# cpu-68000.net
KiCad netlist of a schematic drawn in EAGLE
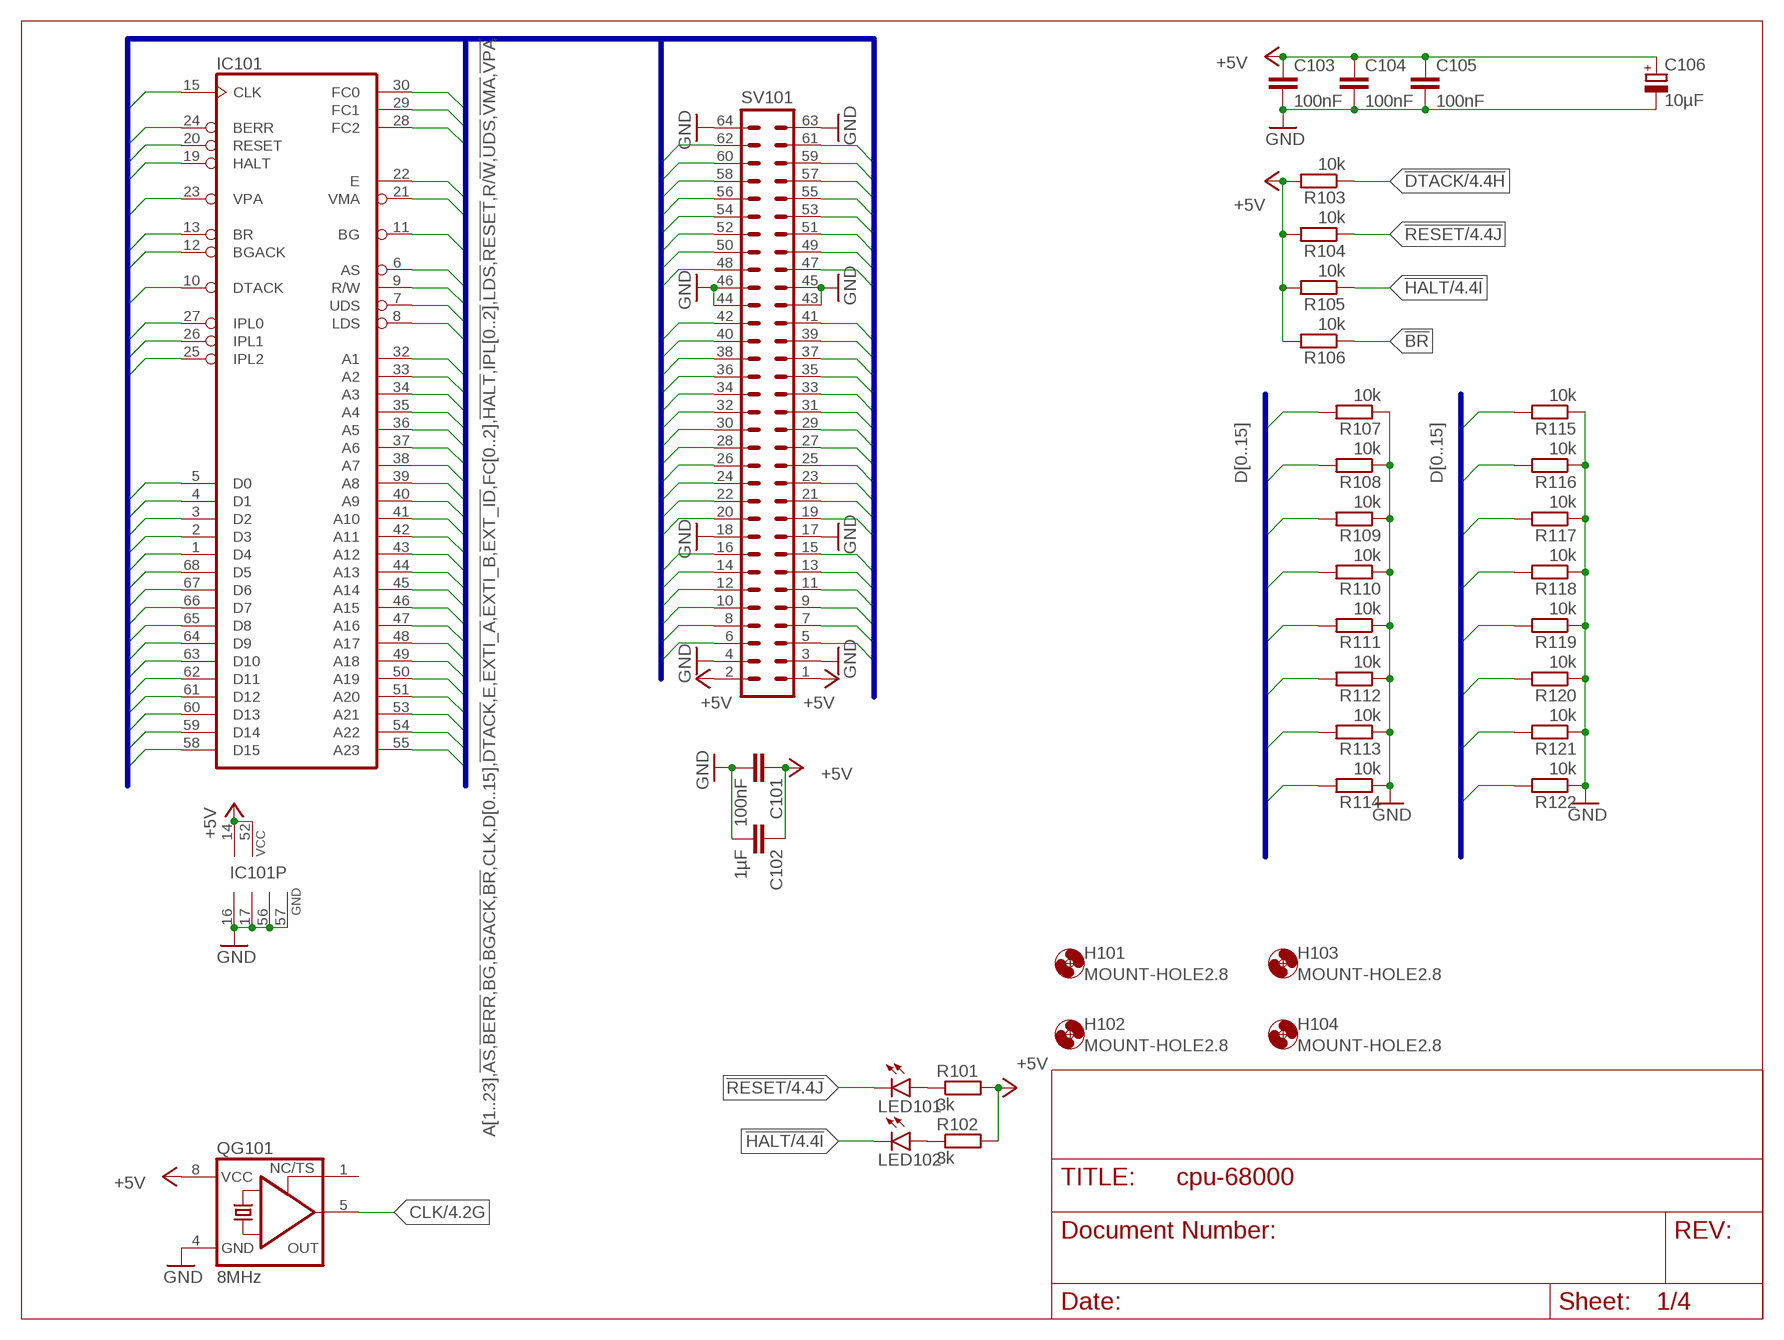
[diagram p0: schematic, sheet 1]
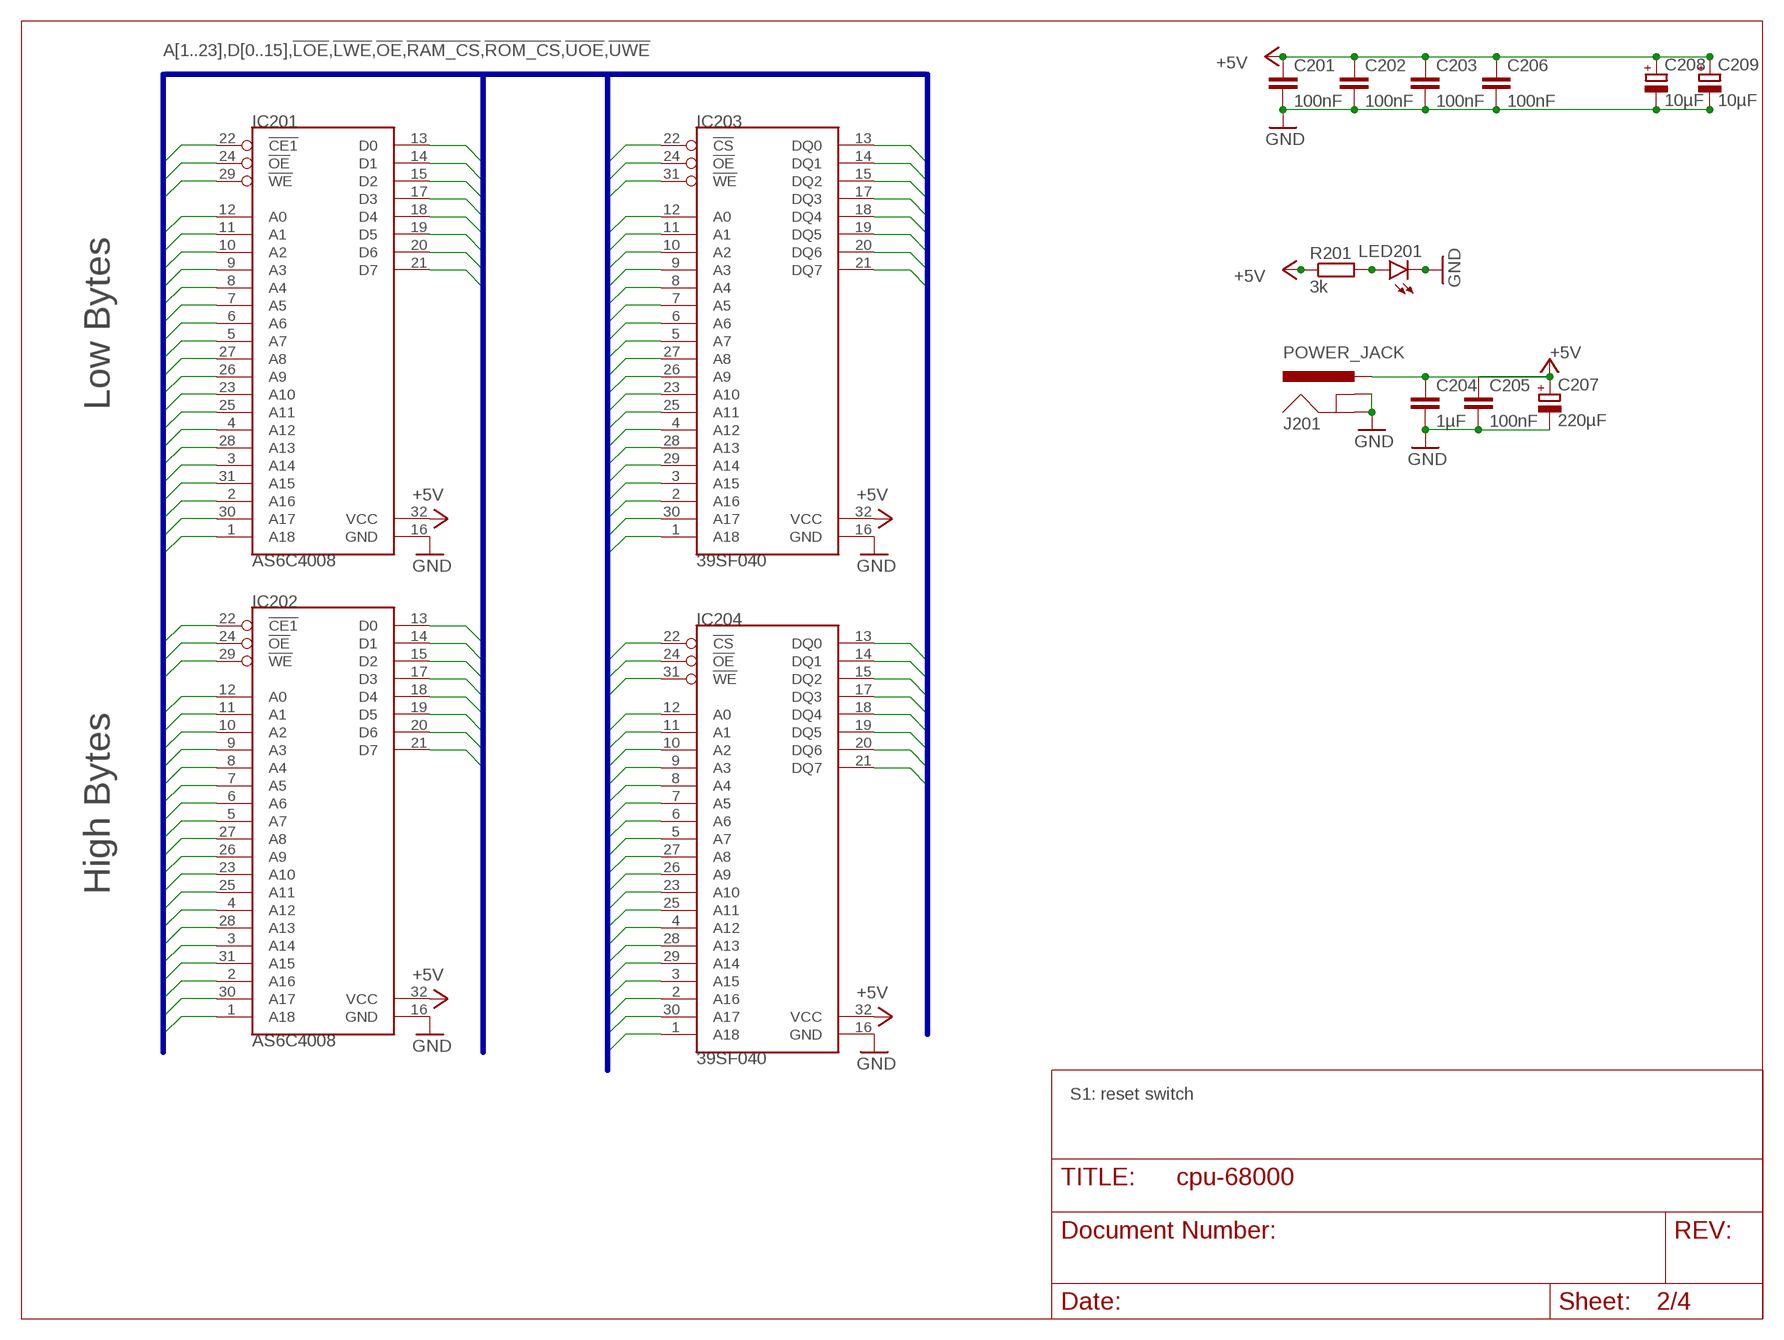
[diagram p1: schematic, sheet 2]
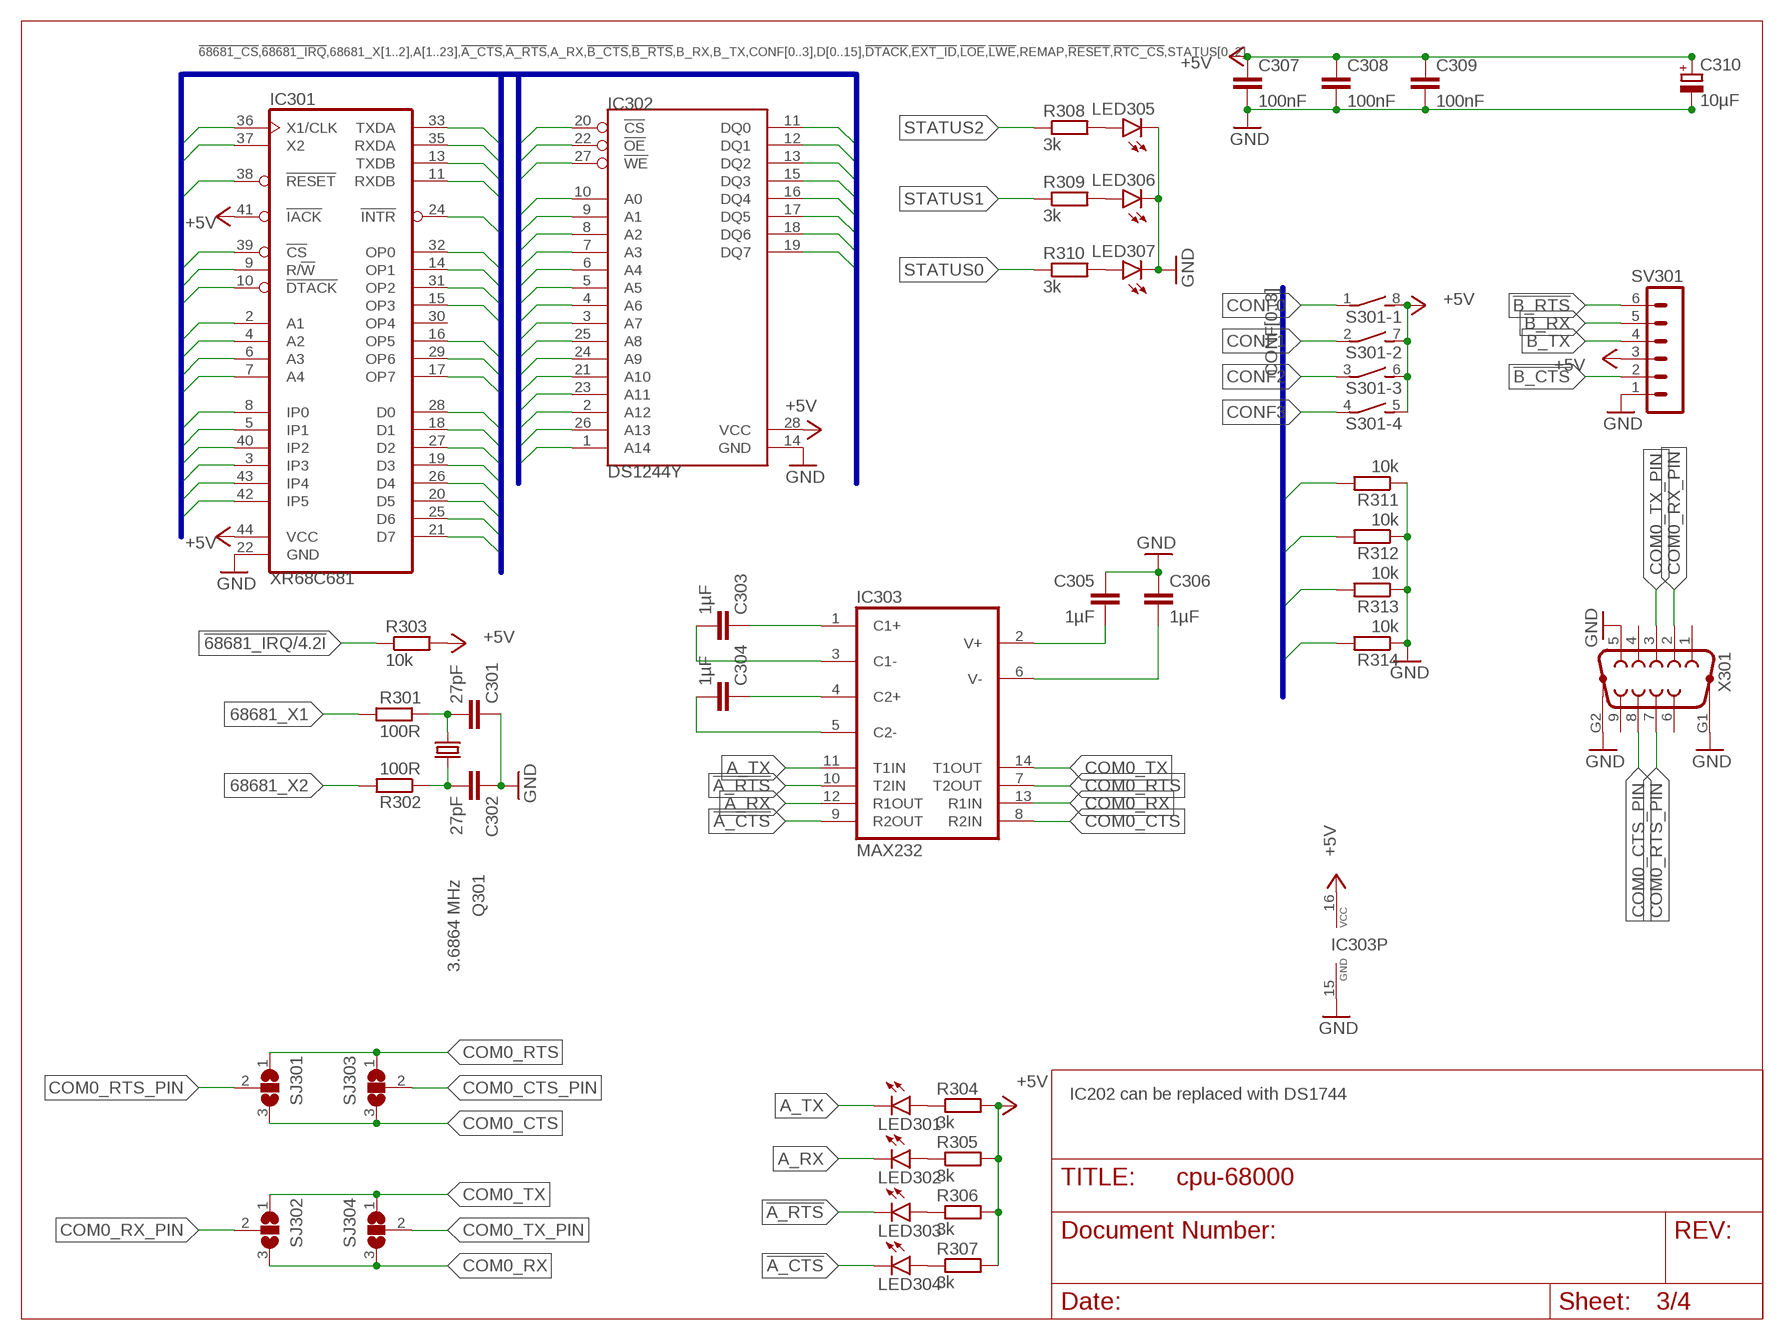
[diagram p2: schematic, sheet 3]
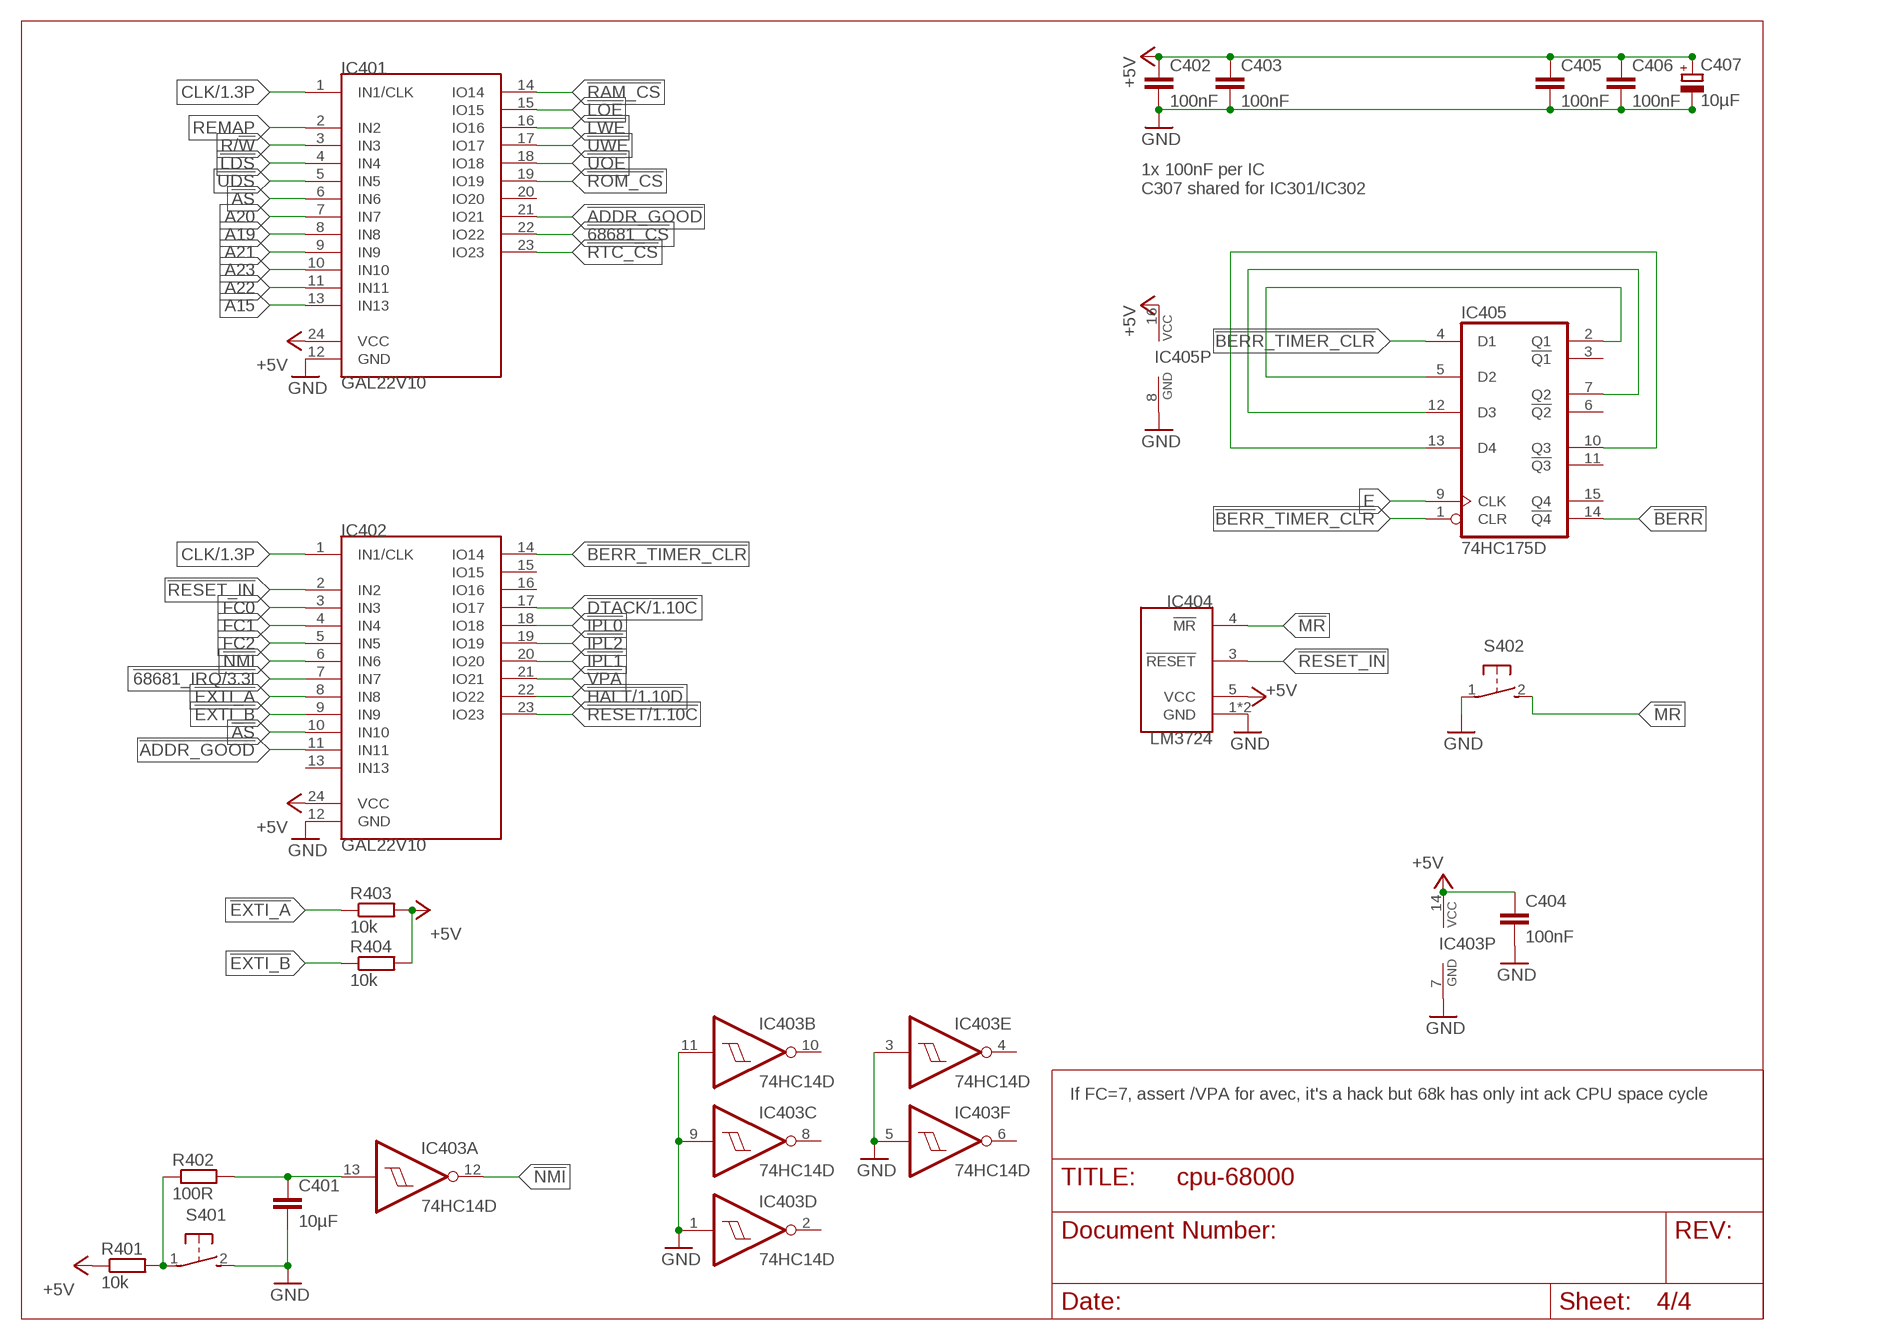
[diagram p3: schematic, sheet 4]

(export (version "E")
  (design (tool "Eeschema 10.0.6"))
  (components
    (comp (ref "C301")
      (value "27pF")
      (footprint "eagle-import:C0805")
      (libsource (lib "eagle-import") (part "C-EUC0805"))
    )
    (comp (ref "C302")
      (value "27pF")
      (footprint "eagle-import:C0805")
      (libsource (lib "eagle-import") (part "C-EUC0805"))
    )
    (comp (ref "C303")
      (value "1µF")
      (footprint "eagle-import:C0805")
      (libsource (lib "eagle-import") (part "C-EUC0805"))
    )
    (comp (ref "C304")
      (value "1µF")
      (footprint "eagle-import:C0805")
      (libsource (lib "eagle-import") (part "C-EUC0805"))
    )
    (comp (ref "C305")
      (value "1µF")
      (footprint "eagle-import:C0805")
      (libsource (lib "eagle-import") (part "C-EUC0805"))
    )
    (comp (ref "C306")
      (value "1µF")
      (footprint "eagle-import:C0805")
      (libsource (lib "eagle-import") (part "C-EUC0805"))
    )
    (comp (ref "C307")
      (value "100nF")
      (footprint "eagle-import:C0805")
      (libsource (lib "eagle-import") (part "C-EUC0805"))
    )
    (comp (ref "C308")
      (value "100nF")
      (footprint "eagle-import:C0805")
      (libsource (lib "eagle-import") (part "C-EUC0805"))
    )
    (comp (ref "C309")
      (value "100nF")
      (footprint "eagle-import:C0805")
      (libsource (lib "eagle-import") (part "C-EUC0805"))
    )
    (comp (ref "C310")
      (value "10µF")
      (footprint "eagle-import:SMC_B")
      (libsource (lib "eagle-import") (part "CPOL-EUSMCB"))
    )
    (comp (ref "IC301")
      (value "XR68C681")
      (footprint "eagle-import:PLCC-S44")
      (libsource (lib "eagle-import") (part "MC68681PLCC44-SOCKET"))
    )
    (comp (ref "IC302")
      (value "DS1244Y")
      (footprint "eagle-import:DIL28-6")
      (libsource (lib "eagle-import") (part "DS1244EDIP-28"))
    )
    (comp (ref "IC303")
      (value "MAX232")
      (footprint "eagle-import:DIL16")
      (fields
        (field (name "MF") "MAXIM")
        (field (name "MPN") "MAX232ACPE+")
        (field (name "MOUSER") "595-MAX232ECN")
        (field (name "MOUSER_SOCKET") "575-1104731641001000")
      )
      (libsource (lib "eagle-import") (part "MAX232"))
    )
    (comp (ref "LED301")
      (value "LEDCHIPLED_1206")
      (footprint "eagle-import:CHIPLED_1206")
      (libsource (lib "eagle-import") (part "LEDCHIPLED_1206"))
    )
    (comp (ref "LED302")
      (value "LEDCHIPLED_1206")
      (footprint "eagle-import:CHIPLED_1206")
      (libsource (lib "eagle-import") (part "LEDCHIPLED_1206"))
    )
    (comp (ref "LED303")
      (value "LEDCHIPLED_1206")
      (footprint "eagle-import:CHIPLED_1206")
      (libsource (lib "eagle-import") (part "LEDCHIPLED_1206"))
    )
    (comp (ref "LED304")
      (value "LEDCHIPLED_1206")
      (footprint "eagle-import:CHIPLED_1206")
      (libsource (lib "eagle-import") (part "LEDCHIPLED_1206"))
    )
    (comp (ref "LED305")
      (value "LEDCHIPLED_1206")
      (footprint "eagle-import:CHIPLED_1206")
      (libsource (lib "eagle-import") (part "LEDCHIPLED_1206"))
    )
    (comp (ref "LED306")
      (value "LEDCHIPLED_1206")
      (footprint "eagle-import:CHIPLED_1206")
      (libsource (lib "eagle-import") (part "LEDCHIPLED_1206"))
    )
    (comp (ref "LED307")
      (value "LEDCHIPLED_1206")
      (footprint "eagle-import:CHIPLED_1206")
      (libsource (lib "eagle-import") (part "LEDCHIPLED_1206"))
    )
    (comp (ref "Q301")
      (value "3.6864 MHz")
      (footprint "eagle-import:HC49_S")
      (libsource (lib "eagle-import") (part "CRYSTALHC49S"))
    )
    (comp (ref "R301")
      (value "100R")
      (footprint "eagle-import:R2012")
      (libsource (lib "eagle-import") (part "R-EU_R2012"))
    )
    (comp (ref "R302")
      (value "100R")
      (footprint "eagle-import:R2012")
      (libsource (lib "eagle-import") (part "R-EU_R2012"))
    )
    (comp (ref "R303")
      (value "10k")
      (footprint "eagle-import:R2012")
      (libsource (lib "eagle-import") (part "R-EU_R2012"))
    )
    (comp (ref "R304")
      (value "3k")
      (footprint "eagle-import:R2012")
      (libsource (lib "eagle-import") (part "R-EU_R2012"))
    )
    (comp (ref "R305")
      (value "3k")
      (footprint "eagle-import:R2012")
      (libsource (lib "eagle-import") (part "R-EU_R2012"))
    )
    (comp (ref "R306")
      (value "3k")
      (footprint "eagle-import:R2012")
      (libsource (lib "eagle-import") (part "R-EU_R2012"))
    )
    (comp (ref "R307")
      (value "3k")
      (footprint "eagle-import:R2012")
      (libsource (lib "eagle-import") (part "R-EU_R2012"))
    )
    (comp (ref "R308")
      (value "3k")
      (footprint "eagle-import:R2012")
      (libsource (lib "eagle-import") (part "R-EU_R2012"))
    )
    (comp (ref "R309")
      (value "3k")
      (footprint "eagle-import:R2012")
      (libsource (lib "eagle-import") (part "R-EU_R2012"))
    )
    (comp (ref "R310")
      (value "3k")
      (footprint "eagle-import:R2012")
      (libsource (lib "eagle-import") (part "R-EU_R2012"))
    )
    (comp (ref "R311")
      (value "10k")
      (footprint "eagle-import:R2012")
      (libsource (lib "eagle-import") (part "R-EU_R2012"))
    )
    (comp (ref "R312")
      (value "10k")
      (footprint "eagle-import:R2012")
      (libsource (lib "eagle-import") (part "R-EU_R2012"))
    )
    (comp (ref "R313")
      (value "10k")
      (footprint "eagle-import:R2012")
      (libsource (lib "eagle-import") (part "R-EU_R2012"))
    )
    (comp (ref "R314")
      (value "10k")
      (footprint "eagle-import:R2012")
      (libsource (lib "eagle-import") (part "R-EU_R2012"))
    )
    (comp (ref "S301")
      (value "DIP04S")
      (footprint "eagle-import:DIP04S")
      (fields (field (name "MOUSER") "653-A6FR-4104"))
      (libsource (lib "eagle-import") (part "DIP04S"))
    )
    (comp (ref "SJ301")
      (value "SJ2WW")
      (footprint "eagle-import:SJ_2W")
      (libsource (lib "eagle-import") (part "SJ2WW"))
    )
    (comp (ref "SJ302")
      (value "SJ2WW")
      (footprint "eagle-import:SJ_2W")
      (libsource (lib "eagle-import") (part "SJ2WW"))
    )
    (comp (ref "SJ303")
      (value "SJ2WW")
      (footprint "eagle-import:SJ_2W")
      (libsource (lib "eagle-import") (part "SJ2WW"))
    )
    (comp (ref "SJ304")
      (value "SJ2WW")
      (footprint "eagle-import:SJ_2W")
      (libsource (lib "eagle-import") (part "SJ2WW"))
    )
    (comp (ref "SV301")
      (value "MA06-1")
      (footprint "eagle-import:MA06-1")
      (libsource (lib "eagle-import") (part "MA06-1"))
    )
    (comp (ref "X301")
      (value "F09HP")
      (footprint "eagle-import:F09HP")
      (libsource (lib "eagle-import") (part "F09HP"))
    )
    (comp (ref "C101")
      (value "100nF")
      (footprint "eagle-import:C0805")
      (libsource (lib "eagle-import") (part "C-EUC0805"))
    )
    (comp (ref "C102")
      (value "1µF")
      (footprint "eagle-import:C0805")
      (libsource (lib "eagle-import") (part "C-EUC0805"))
    )
    (comp (ref "C103")
      (value "100nF")
      (footprint "eagle-import:C0805")
      (libsource (lib "eagle-import") (part "C-EUC0805"))
    )
    (comp (ref "C104")
      (value "100nF")
      (footprint "eagle-import:C0805")
      (libsource (lib "eagle-import") (part "C-EUC0805"))
    )
    (comp (ref "C105")
      (value "100nF")
      (footprint "eagle-import:C0805")
      (libsource (lib "eagle-import") (part "C-EUC0805"))
    )
    (comp (ref "C106")
      (value "10µF")
      (footprint "eagle-import:SMC_B")
      (libsource (lib "eagle-import") (part "CPOL-EUSMCB"))
    )
    (comp (ref "H101")
      (value "MOUNT-HOLE2.8")
      (footprint "eagle-import:2,8")
      (libsource (lib "eagle-import") (part "MOUNT-HOLE2.8"))
    )
    (comp (ref "H102")
      (value "MOUNT-HOLE2.8")
      (footprint "eagle-import:2,8")
      (libsource (lib "eagle-import") (part "MOUNT-HOLE2.8"))
    )
    (comp (ref "H103")
      (value "MOUNT-HOLE2.8")
      (footprint "eagle-import:2,8")
      (libsource (lib "eagle-import") (part "MOUNT-HOLE2.8"))
    )
    (comp (ref "H104")
      (value "MOUNT-HOLE2.8")
      (footprint "eagle-import:2,8")
      (libsource (lib "eagle-import") (part "MOUNT-HOLE2.8"))
    )
    (comp (ref "IC101")
      (value "MC68000FN-SOC")
      (footprint "eagle-import:PLCC68SOCK")
      (fields (field (name "MOUSER_SOCKET") "940-44-068-24-000000"))
      (libsource (lib "eagle-import") (part "MC68000FN-SOC"))
    )
    (comp (ref "LED101")
      (value "LEDCHIPLED_1206")
      (footprint "eagle-import:CHIPLED_1206")
      (libsource (lib "eagle-import") (part "LEDCHIPLED_1206"))
    )
    (comp (ref "LED102")
      (value "LEDCHIPLED_1206")
      (footprint "eagle-import:CHIPLED_1206")
      (libsource (lib "eagle-import") (part "LEDCHIPLED_1206"))
    )
    (comp (ref "QG101")
      (value "8MHz")
      (footprint "eagle-import:DIL08S")
      (libsource (lib "eagle-import") (part "XO-8"))
    )
    (comp (ref "R101")
      (value "3k")
      (footprint "eagle-import:R2012")
      (libsource (lib "eagle-import") (part "R-EU_R2012"))
    )
    (comp (ref "R102")
      (value "3k")
      (footprint "eagle-import:R2012")
      (libsource (lib "eagle-import") (part "R-EU_R2012"))
    )
    (comp (ref "R103")
      (value "10k")
      (footprint "eagle-import:R2012")
      (libsource (lib "eagle-import") (part "R-EU_R2012"))
    )
    (comp (ref "R104")
      (value "10k")
      (footprint "eagle-import:R2012")
      (libsource (lib "eagle-import") (part "R-EU_R2012"))
    )
    (comp (ref "R105")
      (value "10k")
      (footprint "eagle-import:R2012")
      (libsource (lib "eagle-import") (part "R-EU_R2012"))
    )
    (comp (ref "R106")
      (value "10k")
      (footprint "eagle-import:R2012")
      (libsource (lib "eagle-import") (part "R-EU_R2012"))
    )
    (comp (ref "R107")
      (value "10k")
      (footprint "eagle-import:R2012")
      (libsource (lib "eagle-import") (part "R-EU_R2012"))
    )
    (comp (ref "R108")
      (value "10k")
      (footprint "eagle-import:R2012")
      (libsource (lib "eagle-import") (part "R-EU_R2012"))
    )
    (comp (ref "R109")
      (value "10k")
      (footprint "eagle-import:R2012")
      (libsource (lib "eagle-import") (part "R-EU_R2012"))
    )
    (comp (ref "R110")
      (value "10k")
      (footprint "eagle-import:R2012")
      (libsource (lib "eagle-import") (part "R-EU_R2012"))
    )
    (comp (ref "R111")
      (value "10k")
      (footprint "eagle-import:R2012")
      (libsource (lib "eagle-import") (part "R-EU_R2012"))
    )
    (comp (ref "R112")
      (value "10k")
      (footprint "eagle-import:R2012")
      (libsource (lib "eagle-import") (part "R-EU_R2012"))
    )
    (comp (ref "R113")
      (value "10k")
      (footprint "eagle-import:R2012")
      (libsource (lib "eagle-import") (part "R-EU_R2012"))
    )
    (comp (ref "R114")
      (value "10k")
      (footprint "eagle-import:R2012")
      (libsource (lib "eagle-import") (part "R-EU_R2012"))
    )
    (comp (ref "R115")
      (value "10k")
      (footprint "eagle-import:R2012")
      (libsource (lib "eagle-import") (part "R-EU_R2012"))
    )
    (comp (ref "R116")
      (value "10k")
      (footprint "eagle-import:R2012")
      (libsource (lib "eagle-import") (part "R-EU_R2012"))
    )
    (comp (ref "R117")
      (value "10k")
      (footprint "eagle-import:R2012")
      (libsource (lib "eagle-import") (part "R-EU_R2012"))
    )
    (comp (ref "R118")
      (value "10k")
      (footprint "eagle-import:R2012")
      (libsource (lib "eagle-import") (part "R-EU_R2012"))
    )
    (comp (ref "R119")
      (value "10k")
      (footprint "eagle-import:R2012")
      (libsource (lib "eagle-import") (part "R-EU_R2012"))
    )
    (comp (ref "R120")
      (value "10k")
      (footprint "eagle-import:R2012")
      (libsource (lib "eagle-import") (part "R-EU_R2012"))
    )
    (comp (ref "R121")
      (value "10k")
      (footprint "eagle-import:R2012")
      (libsource (lib "eagle-import") (part "R-EU_R2012"))
    )
    (comp (ref "R122")
      (value "10k")
      (footprint "eagle-import:R2012")
      (libsource (lib "eagle-import") (part "R-EU_R2012"))
    )
    (comp (ref "SV101")
      (value "ML64L")
      (footprint "eagle-import:ML64L")
      (libsource (lib "eagle-import") (part "ML64L"))
    )
    (comp (ref "C401")
      (value "10µF")
      (footprint "eagle-import:C0805")
      (libsource (lib "eagle-import") (part "C-EUC0805"))
    )
    (comp (ref "C402")
      (value "100nF")
      (footprint "eagle-import:C0805")
      (libsource (lib "eagle-import") (part "C-EUC0805"))
    )
    (comp (ref "C403")
      (value "100nF")
      (footprint "eagle-import:C0805")
      (libsource (lib "eagle-import") (part "C-EUC0805"))
    )
    (comp (ref "C404")
      (value "100nF")
      (footprint "eagle-import:C0805")
      (libsource (lib "eagle-import") (part "C-EUC0805"))
    )
    (comp (ref "C405")
      (value "100nF")
      (footprint "eagle-import:C0805")
      (libsource (lib "eagle-import") (part "C-EUC0805"))
    )
    (comp (ref "C406")
      (value "100nF")
      (footprint "eagle-import:C0805")
      (libsource (lib "eagle-import") (part "C-EUC0805"))
    )
    (comp (ref "C407")
      (value "10µF")
      (footprint "eagle-import:SMC_B")
      (libsource (lib "eagle-import") (part "CPOL-EUSMCB"))
    )
    (comp (ref "IC401")
      (value "GAL22V10")
      (footprint "eagle-import:DIL24S")
      (libsource (lib "eagle-import") (part "GAL22V10DIP24"))
    )
    (comp (ref "IC402")
      (value "GAL22V10")
      (footprint "eagle-import:DIL24S")
      (libsource (lib "eagle-import") (part "GAL22V10DIP24"))
    )
    (comp (ref "IC403")
      (value "74HC14D")
      (footprint "eagle-import:SO14")
      (fields (field (name "MOUSER") "771-74HC14D-T"))
      (libsource (lib "eagle-import") (part "7414DHC"))
    )
    (comp (ref "IC404")
      (value "LM3724")
      (footprint "eagle-import:SOT23-5")
      (libsource (lib "eagle-import") (part "LM3724"))
    )
    (comp (ref "IC405")
      (value "74HC175D")
      (footprint "eagle-import:SO16")
      (fields (field (name "MOUSER") "595-CD74HCT175M"))
      (libsource (lib "eagle-import") (part "74175DHC"))
    )
    (comp (ref "R401")
      (value "10k")
      (footprint "eagle-import:R2012")
      (libsource (lib "eagle-import") (part "R-EU_R2012"))
    )
    (comp (ref "R402")
      (value "100R")
      (footprint "eagle-import:R2012")
      (libsource (lib "eagle-import") (part "R-EU_R2012"))
    )
    (comp (ref "R403")
      (value "10k")
      (footprint "eagle-import:R2012")
      (libsource (lib "eagle-import") (part "R-EU_R2012"))
    )
    (comp (ref "R404")
      (value "10k")
      (footprint "eagle-import:R2012")
      (libsource (lib "eagle-import") (part "R-EU_R2012"))
    )
    (comp (ref "S401")
      (value "31-XX")
      (footprint "eagle-import:B3F-31XX")
      (fields (field (name "MPN") "B3F-3100") (field (name "SPICEPREFIX") "S"))
      (libsource (lib "eagle-import") (part "31-XX"))
    )
    (comp (ref "S402")
      (value "31-XX")
      (footprint "eagle-import:B3F-31XX")
      (fields (field (name "MPN") "B3F-3100"))
      (libsource (lib "eagle-import") (part "31-XX"))
    )
    (comp (ref "C201")
      (value "100nF")
      (footprint "eagle-import:C0805")
      (libsource (lib "eagle-import") (part "C-EUC0805"))
    )
    (comp (ref "C202")
      (value "100nF")
      (footprint "eagle-import:C0805")
      (libsource (lib "eagle-import") (part "C-EUC0805"))
    )
    (comp (ref "C203")
      (value "100nF")
      (footprint "eagle-import:C0805")
      (libsource (lib "eagle-import") (part "C-EUC0805"))
    )
    (comp (ref "C204")
      (value "1µF")
      (footprint "eagle-import:C0805")
      (libsource (lib "eagle-import") (part "C-EUC0805"))
    )
    (comp (ref "C205")
      (value "100nF")
      (footprint "eagle-import:C0805")
      (libsource (lib "eagle-import") (part "C-EUC0805"))
    )
    (comp (ref "C206")
      (value "100nF")
      (footprint "eagle-import:C0805")
      (libsource (lib "eagle-import") (part "C-EUC0805"))
    )
    (comp (ref "C207")
      (value "220µF")
      (footprint "eagle-import:E2,5-7")
      (libsource (lib "eagle-import") (part "CPOL-EUE2.5-7"))
    )
    (comp (ref "C208")
      (value "10µF")
      (footprint "eagle-import:SMC_B")
      (libsource (lib "eagle-import") (part "CPOL-EUSMCB"))
    )
    (comp (ref "C209")
      (value "10µF")
      (footprint "eagle-import:SMC_B")
      (libsource (lib "eagle-import") (part "CPOL-EUSMCB"))
    )
    (comp (ref "IC201")
      (value "AS6C4008")
      (footprint "eagle-import:DIL32")
      (libsource (lib "eagle-import") (part "AS6C4008"))
    )
    (comp (ref "IC202")
      (value "AS6C4008")
      (footprint "eagle-import:DIL32")
      (libsource (lib "eagle-import") (part "AS6C4008"))
    )
    (comp (ref "IC203")
      (value "39SF040")
      (footprint "eagle-import:DIL32")
      (fields (field (name "MOUSER") "804-39SF0407CPHE"))
      (libsource (lib "eagle-import") (part "SST39SF0X0PDIP32"))
    )
    (comp (ref "IC204")
      (value "39SF040")
      (footprint "eagle-import:DIL32")
      (fields (field (name "MOUSER") "804-39SF0407CPHE"))
      (libsource (lib "eagle-import") (part "SST39SF0X0PDIP32"))
    )
    (comp (ref "J201")
      (value "POWER_JACK")
      (footprint "eagle-import:POWER_JACK_PTH")
      (libsource (lib "eagle-import") (part "POWER_JACK"))
    )
    (comp (ref "LED201")
      (value "LEDCHIPLED_1206")
      (footprint "eagle-import:CHIPLED_1206")
      (libsource (lib "eagle-import") (part "LEDCHIPLED_1206"))
    )
    (comp (ref "R201")
      (value "3k")
      (footprint "eagle-import:R2012")
      (libsource (lib "eagle-import") (part "R-EU_R2012"))
    )
  )
  (nets
    (net (code "3") (name "+5V") (class "Default")
      (node (ref "C101") (pin "1") (pinfunction "1_1") (pintype "passive"))
      (node (ref "C102") (pin "1") (pinfunction "1_1") (pintype "passive"))
      (node (ref "C103") (pin "1") (pinfunction "1_1") (pintype "passive"))
      (node (ref "C104") (pin "1") (pinfunction "1_1") (pintype "passive"))
      (node (ref "C105") (pin "1") (pinfunction "1_1") (pintype "passive"))
      (node (ref "C106") (pin "+") (pinfunction "+_+") (pintype "passive"))
      (node (ref "C201") (pin "1") (pinfunction "1_1") (pintype "passive"))
      (node (ref "C202") (pin "1") (pinfunction "1_1") (pintype "passive"))
      (node (ref "C203") (pin "1") (pinfunction "1_1") (pintype "passive"))
      (node (ref "C204") (pin "1") (pinfunction "1_1") (pintype "passive"))
      (node (ref "C205") (pin "1") (pinfunction "1_1") (pintype "passive"))
      (node (ref "C206") (pin "1") (pinfunction "1_1") (pintype "passive"))
      (node (ref "C207") (pin "+") (pinfunction "+_+") (pintype "passive"))
      (node (ref "C208") (pin "+") (pinfunction "+_+") (pintype "passive"))
      (node (ref "C209") (pin "+") (pinfunction "+_+") (pintype "passive"))
      (node (ref "C307") (pin "1") (pinfunction "1_1") (pintype "passive"))
      (node (ref "C308") (pin "1") (pinfunction "1_1") (pintype "passive"))
      (node (ref "C309") (pin "1") (pinfunction "1_1") (pintype "passive"))
      (node (ref "C310") (pin "+") (pinfunction "+_+") (pintype "passive"))
      (node (ref "C402") (pin "1") (pinfunction "1_1") (pintype "passive"))
      (node (ref "C403") (pin "1") (pinfunction "1_1") (pintype "passive"))
      (node (ref "C404") (pin "1") (pinfunction "1_1") (pintype "passive"))
      (node (ref "C405") (pin "1") (pinfunction "1_1") (pintype "passive"))
      (node (ref "C406") (pin "1") (pinfunction "1_1") (pintype "passive"))
      (node (ref "C407") (pin "+") (pinfunction "+_+") (pintype "passive"))
      (node (ref "IC101") (pin "14") (pinfunction "VCC_14") (pintype "power_in"))
      (node (ref "IC101") (pin "52") (pinfunction "VCC_52") (pintype "power_in"))
      (node (ref "IC201") (pin "32") (pinfunction "VCC_32") (pintype "power_in"))
      (node (ref "IC202") (pin "32") (pinfunction "VCC_32") (pintype "power_in"))
      (node (ref "IC203") (pin "32") (pinfunction "VCC_32") (pintype "power_in"))
      (node (ref "IC204") (pin "32") (pinfunction "VCC_32") (pintype "power_in"))
      (node (ref "IC301") (pin "41") (pinfunction "~{IACK}_41") (pintype "input"))
      (node (ref "IC301") (pin "44") (pinfunction "VCC_44") (pintype "power_in"))
      (node (ref "IC302") (pin "28") (pinfunction "VCC_28") (pintype "power_in"))
      (node (ref "IC303") (pin "16") (pinfunction "VCC_16") (pintype "power_in"))
      (node (ref "IC401") (pin "24") (pinfunction "VCC_24") (pintype "power_in"))
      (node (ref "IC402") (pin "24") (pinfunction "VCC_24") (pintype "power_in"))
      (node (ref "IC403") (pin "14") (pinfunction "VCC_14") (pintype "power_in"))
      (node (ref "IC404") (pin "5") (pinfunction "VCC_5") (pintype "power_in"))
      (node (ref "IC405") (pin "16") (pinfunction "VCC_16") (pintype "power_in"))
      (node (ref "J201") (pin "PWR") (pinfunction "PWR_PWR") (pintype "bidirectional"))
      (node (ref "QG101") (pin "8") (pinfunction "VCC_8") (pintype "power_in"))
      (node (ref "R101") (pin "2") (pinfunction "2_2") (pintype "passive"))
      (node (ref "R102") (pin "2") (pinfunction "2_2") (pintype "passive"))
      (node (ref "R103") (pin "2") (pinfunction "2_2") (pintype "passive"))
      (node (ref "R104") (pin "2") (pinfunction "2_2") (pintype "passive"))
      (node (ref "R105") (pin "2") (pinfunction "2_2") (pintype "passive"))
      (node (ref "R106") (pin "2") (pinfunction "2_2") (pintype "passive"))
      (node (ref "R201") (pin "1") (pinfunction "1_1") (pintype "passive"))
      (node (ref "R303") (pin "2") (pinfunction "2_2") (pintype "passive"))
      (node (ref "R304") (pin "2") (pinfunction "2_2") (pintype "passive"))
      (node (ref "R305") (pin "2") (pinfunction "2_2") (pintype "passive"))
      (node (ref "R306") (pin "2") (pinfunction "2_2") (pintype "passive"))
      (node (ref "R307") (pin "2") (pinfunction "2_2") (pintype "passive"))
      (node (ref "R401") (pin "1") (pinfunction "1_1") (pintype "passive"))
      (node (ref "R403") (pin "2") (pinfunction "2_2") (pintype "passive"))
      (node (ref "R404") (pin "2") (pinfunction "2_2") (pintype "passive"))
      (node (ref "S301") (pin "5") (pinfunction "2_5") (pintype "passive"))
      (node (ref "S301") (pin "6") (pinfunction "2_6") (pintype "passive"))
      (node (ref "S301") (pin "7") (pinfunction "2_7") (pintype "passive"))
      (node (ref "S301") (pin "8") (pinfunction "2_8") (pintype "passive"))
      (node (ref "SV101") (pin "1") (pinfunction "1_1") (pintype "passive"))
      (node (ref "SV101") (pin "2") (pinfunction "2_2") (pintype "passive"))
      (node (ref "SV301") (pin "3") (pinfunction "3_3") (pintype "passive"))
    )
    (net (code "9") (name "68681_X1") (class "Default")
      (node (ref "IC301") (pin "36") (pinfunction "X1/CLK_36") (pintype "input"))
      (node (ref "R301") (pin "2") (pinfunction "2_2") (pintype "passive"))
    )
    (net (code "10") (name "68681_X2") (class "Default")
      (node (ref "IC301") (pin "37") (pinfunction "X2_37") (pintype "output"))
      (node (ref "R302") (pin "2") (pinfunction "2_2") (pintype "passive"))
    )
    (net (code "11") (name "A1") (class "Default")
      (node (ref "IC101") (pin "32") (pinfunction "A1_32") (pintype "output"))
      (node (ref "IC201") (pin "12") (pinfunction "A0_12") (pintype "input"))
      (node (ref "IC202") (pin "12") (pinfunction "A0_12") (pintype "input"))
      (node (ref "IC203") (pin "12") (pinfunction "A0_12") (pintype "input"))
      (node (ref "IC204") (pin "12") (pinfunction "A0_12") (pintype "input"))
      (node (ref "IC301") (pin "2") (pinfunction "A1_2") (pintype "input"))
      (node (ref "IC302") (pin "10") (pinfunction "A0_10") (pintype "input"))
      (node (ref "SV101") (pin "20") (pinfunction "20_20") (pintype "passive"))
    )
    (net (code "12") (name "A2") (class "Default")
      (node (ref "IC101") (pin "33") (pinfunction "A2_33") (pintype "output"))
      (node (ref "IC201") (pin "11") (pinfunction "A1_11") (pintype "input"))
      (node (ref "IC202") (pin "11") (pinfunction "A1_11") (pintype "input"))
      (node (ref "IC203") (pin "11") (pinfunction "A1_11") (pintype "input"))
      (node (ref "IC204") (pin "11") (pinfunction "A1_11") (pintype "input"))
      (node (ref "IC301") (pin "4") (pinfunction "A2_4") (pintype "input"))
      (node (ref "IC302") (pin "9") (pinfunction "A1_9") (pintype "input"))
      (node (ref "SV101") (pin "22") (pinfunction "22_22") (pintype "passive"))
    )
    (net (code "13") (name "A3") (class "Default")
      (node (ref "IC101") (pin "34") (pinfunction "A3_34") (pintype "output"))
      (node (ref "IC201") (pin "10") (pinfunction "A2_10") (pintype "input"))
      (node (ref "IC202") (pin "10") (pinfunction "A2_10") (pintype "input"))
      (node (ref "IC203") (pin "10") (pinfunction "A2_10") (pintype "input"))
      (node (ref "IC204") (pin "10") (pinfunction "A2_10") (pintype "input"))
      (node (ref "IC301") (pin "6") (pinfunction "A3_6") (pintype "input"))
      (node (ref "IC302") (pin "8") (pinfunction "A2_8") (pintype "input"))
      (node (ref "SV101") (pin "19") (pinfunction "19_19") (pintype "passive"))
    )
    (net (code "14") (name "A4") (class "Default")
      (node (ref "IC101") (pin "35") (pinfunction "A4_35") (pintype "output"))
      (node (ref "IC201") (pin "9") (pinfunction "A3_9") (pintype "input"))
      (node (ref "IC202") (pin "9") (pinfunction "A3_9") (pintype "input"))
      (node (ref "IC203") (pin "9") (pinfunction "A3_9") (pintype "input"))
      (node (ref "IC204") (pin "9") (pinfunction "A3_9") (pintype "input"))
      (node (ref "IC301") (pin "7") (pinfunction "A4_7") (pintype "input"))
      (node (ref "IC302") (pin "7") (pinfunction "A3_7") (pintype "input"))
      (node (ref "SV101") (pin "24") (pinfunction "24_24") (pintype "passive"))
    )
    (net (code "15") (name "A5") (class "Default")
      (node (ref "IC101") (pin "36") (pinfunction "A5_36") (pintype "output"))
      (node (ref "IC201") (pin "8") (pinfunction "A4_8") (pintype "input"))
      (node (ref "IC202") (pin "8") (pinfunction "A4_8") (pintype "input"))
      (node (ref "IC203") (pin "8") (pinfunction "A4_8") (pintype "input"))
      (node (ref "IC204") (pin "8") (pinfunction "A4_8") (pintype "input"))
      (node (ref "IC302") (pin "6") (pinfunction "A4_6") (pintype "input"))
      (node (ref "SV101") (pin "21") (pinfunction "21_21") (pintype "passive"))
    )
    (net (code "16") (name "A6") (class "Default")
      (node (ref "IC101") (pin "37") (pinfunction "A6_37") (pintype "output"))
      (node (ref "IC201") (pin "7") (pinfunction "A5_7") (pintype "input"))
      (node (ref "IC202") (pin "7") (pinfunction "A5_7") (pintype "input"))
      (node (ref "IC203") (pin "7") (pinfunction "A5_7") (pintype "input"))
      (node (ref "IC204") (pin "7") (pinfunction "A5_7") (pintype "input"))
      (node (ref "IC302") (pin "5") (pinfunction "A5_5") (pintype "input"))
      (node (ref "SV101") (pin "23") (pinfunction "23_23") (pintype "passive"))
    )
    (net (code "17") (name "A7") (class "Default")
      (node (ref "IC101") (pin "38") (pinfunction "A7_38") (pintype "output"))
      (node (ref "IC201") (pin "6") (pinfunction "A6_6") (pintype "input"))
      (node (ref "IC202") (pin "6") (pinfunction "A6_6") (pintype "input"))
      (node (ref "IC203") (pin "6") (pinfunction "A6_6") (pintype "input"))
      (node (ref "IC204") (pin "6") (pinfunction "A6_6") (pintype "input"))
      (node (ref "IC302") (pin "4") (pinfunction "A6_4") (pintype "input"))
      (node (ref "SV101") (pin "26") (pinfunction "26_26") (pintype "passive"))
    )
    (net (code "18") (name "A8") (class "Default")
      (node (ref "IC101") (pin "39") (pinfunction "A8_39") (pintype "output"))
      (node (ref "IC201") (pin "5") (pinfunction "A7_5") (pintype "input"))
      (node (ref "IC202") (pin "5") (pinfunction "A7_5") (pintype "input"))
      (node (ref "IC203") (pin "5") (pinfunction "A7_5") (pintype "input"))
      (node (ref "IC204") (pin "5") (pinfunction "A7_5") (pintype "input"))
      (node (ref "IC302") (pin "3") (pinfunction "A7_3") (pintype "input"))
      (node (ref "SV101") (pin "25") (pinfunction "25_25") (pintype "passive"))
    )
    (net (code "19") (name "A9") (class "Default")
      (node (ref "IC101") (pin "40") (pinfunction "A9_40") (pintype "output"))
      (node (ref "IC201") (pin "27") (pinfunction "A8_27") (pintype "input"))
      (node (ref "IC202") (pin "27") (pinfunction "A8_27") (pintype "input"))
      (node (ref "IC203") (pin "27") (pinfunction "A8_27") (pintype "input"))
      (node (ref "IC204") (pin "27") (pinfunction "A8_27") (pintype "input"))
      (node (ref "IC302") (pin "25") (pinfunction "A8_25") (pintype "input"))
      (node (ref "SV101") (pin "28") (pinfunction "28_28") (pintype "passive"))
    )
    (net (code "20") (name "A10") (class "Default")
      (node (ref "IC101") (pin "41") (pinfunction "A10_41") (pintype "output"))
      (node (ref "IC201") (pin "26") (pinfunction "A9_26") (pintype "input"))
      (node (ref "IC202") (pin "26") (pinfunction "A9_26") (pintype "input"))
      (node (ref "IC203") (pin "26") (pinfunction "A9_26") (pintype "input"))
      (node (ref "IC204") (pin "26") (pinfunction "A9_26") (pintype "input"))
      (node (ref "IC302") (pin "24") (pinfunction "A9_24") (pintype "input"))
      (node (ref "SV101") (pin "27") (pinfunction "27_27") (pintype "passive"))
    )
    (net (code "21") (name "A11") (class "Default")
      (node (ref "IC101") (pin "42") (pinfunction "A11_42") (pintype "output"))
      (node (ref "IC201") (pin "23") (pinfunction "A10_23") (pintype "input"))
      (node (ref "IC202") (pin "23") (pinfunction "A10_23") (pintype "input"))
      (node (ref "IC203") (pin "23") (pinfunction "A10_23") (pintype "input"))
      (node (ref "IC204") (pin "23") (pinfunction "A10_23") (pintype "input"))
      (node (ref "IC302") (pin "21") (pinfunction "A10_21") (pintype "input"))
      (node (ref "SV101") (pin "30") (pinfunction "30_30") (pintype "passive"))
    )
    (net (code "22") (name "A12") (class "Default")
      (node (ref "IC101") (pin "43") (pinfunction "A12_43") (pintype "output"))
      (node (ref "IC201") (pin "25") (pinfunction "A11_25") (pintype "input"))
      (node (ref "IC202") (pin "25") (pinfunction "A11_25") (pintype "input"))
      (node (ref "IC203") (pin "25") (pinfunction "A11_25") (pintype "input"))
      (node (ref "IC204") (pin "25") (pinfunction "A11_25") (pintype "input"))
      (node (ref "IC302") (pin "23") (pinfunction "A11_23") (pintype "input"))
      (node (ref "SV101") (pin "29") (pinfunction "29_29") (pintype "passive"))
    )
    (net (code "23") (name "A13") (class "Default")
      (node (ref "IC101") (pin "44") (pinfunction "A13_44") (pintype "output"))
      (node (ref "IC201") (pin "4") (pinfunction "A12_4") (pintype "input"))
      (node (ref "IC202") (pin "4") (pinfunction "A12_4") (pintype "input"))
      (node (ref "IC203") (pin "4") (pinfunction "A12_4") (pintype "input"))
      (node (ref "IC204") (pin "4") (pinfunction "A12_4") (pintype "input"))
      (node (ref "IC302") (pin "2") (pinfunction "A12_2") (pintype "input"))
      (node (ref "SV101") (pin "31") (pinfunction "31_31") (pintype "passive"))
    )
    (net (code "24") (name "A14") (class "Default")
      (node (ref "IC101") (pin "45") (pinfunction "A14_45") (pintype "output"))
      (node (ref "IC201") (pin "28") (pinfunction "A13_28") (pintype "input"))
      (node (ref "IC202") (pin "28") (pinfunction "A13_28") (pintype "input"))
      (node (ref "IC203") (pin "28") (pinfunction "A13_28") (pintype "input"))
      (node (ref "IC204") (pin "28") (pinfunction "A13_28") (pintype "input"))
      (node (ref "IC302") (pin "26") (pinfunction "A13_26") (pintype "input"))
      (node (ref "SV101") (pin "32") (pinfunction "32_32") (pintype "passive"))
    )
    (net (code "25") (name "A15") (class "Default")
      (node (ref "IC101") (pin "46") (pinfunction "A15_46") (pintype "output"))
      (node (ref "IC201") (pin "3") (pinfunction "A14_3") (pintype "input"))
      (node (ref "IC202") (pin "3") (pinfunction "A14_3") (pintype "input"))
      (node (ref "IC203") (pin "29") (pinfunction "A14_29") (pintype "input"))
      (node (ref "IC204") (pin "29") (pinfunction "A14_29") (pintype "input"))
      (node (ref "IC302") (pin "1") (pinfunction "A14_1") (pintype "input"))
      (node (ref "IC401") (pin "13") (pinfunction "IN13_13") (pintype "input"))
      (node (ref "SV101") (pin "33") (pinfunction "33_33") (pintype "passive"))
    )
    (net (code "26") (name "A16") (class "Default")
      (node (ref "IC101") (pin "47") (pinfunction "A16_47") (pintype "output"))
      (node (ref "IC201") (pin "31") (pinfunction "A15_31") (pintype "input"))
      (node (ref "IC202") (pin "31") (pinfunction "A15_31") (pintype "input"))
      (node (ref "IC203") (pin "3") (pinfunction "A15_3") (pintype "input"))
      (node (ref "IC204") (pin "3") (pinfunction "A15_3") (pintype "input"))
      (node (ref "SV101") (pin "34") (pinfunction "34_34") (pintype "passive"))
    )
    (net (code "27") (name "A17") (class "Default")
      (node (ref "IC101") (pin "48") (pinfunction "A17_48") (pintype "output"))
      (node (ref "IC201") (pin "2") (pinfunction "A16_2") (pintype "input"))
      (node (ref "IC202") (pin "2") (pinfunction "A16_2") (pintype "input"))
      (node (ref "IC203") (pin "2") (pinfunction "A16_2") (pintype "input"))
      (node (ref "IC204") (pin "2") (pinfunction "A16_2") (pintype "input"))
      (node (ref "SV101") (pin "36") (pinfunction "36_36") (pintype "passive"))
    )
    (net (code "28") (name "A18") (class "Default")
      (node (ref "IC101") (pin "49") (pinfunction "A18_49") (pintype "output"))
      (node (ref "IC201") (pin "30") (pinfunction "A17_30") (pintype "input"))
      (node (ref "IC202") (pin "30") (pinfunction "A17_30") (pintype "input"))
      (node (ref "IC203") (pin "30") (pinfunction "A17_30") (pintype "input"))
      (node (ref "IC204") (pin "30") (pinfunction "A17_30") (pintype "input"))
      (node (ref "SV101") (pin "35") (pinfunction "35_35") (pintype "passive"))
    )
    (net (code "29") (name "A19") (class "Default")
      (node (ref "IC101") (pin "50") (pinfunction "A19_50") (pintype "output"))
      (node (ref "IC201") (pin "1") (pinfunction "A18_1") (pintype "input"))
      (node (ref "IC202") (pin "1") (pinfunction "A18_1") (pintype "input"))
      (node (ref "IC203") (pin "1") (pinfunction "A18_1") (pintype "input"))
      (node (ref "IC204") (pin "1") (pinfunction "A18_1") (pintype "input"))
      (node (ref "IC401") (pin "8") (pinfunction "IN8_8") (pintype "input"))
      (node (ref "SV101") (pin "38") (pinfunction "38_38") (pintype "passive"))
    )
    (net (code "30") (name "A20") (class "Default")
      (node (ref "IC101") (pin "51") (pinfunction "A20_51") (pintype "output"))
      (node (ref "IC401") (pin "7") (pinfunction "IN7_7") (pintype "input"))
      (node (ref "SV101") (pin "37") (pinfunction "37_37") (pintype "passive"))
    )
    (net (code "31") (name "A21") (class "Default")
      (node (ref "IC101") (pin "53") (pinfunction "A21_53") (pintype "output"))
      (node (ref "IC401") (pin "9") (pinfunction "IN9_9") (pintype "input"))
      (node (ref "SV101") (pin "40") (pinfunction "40_40") (pintype "passive"))
    )
    (net (code "32") (name "A22") (class "Default")
      (node (ref "IC101") (pin "54") (pinfunction "A22_54") (pintype "output"))
      (node (ref "IC401") (pin "11") (pinfunction "IN11_11") (pintype "input"))
      (node (ref "SV101") (pin "39") (pinfunction "39_39") (pintype "passive"))
    )
    (net (code "33") (name "A23") (class "Default")
      (node (ref "IC101") (pin "55") (pinfunction "A23_55") (pintype "output"))
      (node (ref "IC401") (pin "10") (pinfunction "IN10_10") (pintype "input"))
      (node (ref "SV101") (pin "42") (pinfunction "42_42") (pintype "passive"))
    )
    (net (code "34") (name "A_RX") (class "Default")
      (node (ref "IC301") (pin "35") (pinfunction "RXDA_35") (pintype "input"))
      (node (ref "IC303") (pin "12") (pinfunction "R1OUT_12") (pintype "output"))
      (node (ref "LED302") (pin "C") (pinfunction "C_C") (pintype "passive"))
    )
    (net (code "35") (name "A_TX") (class "Default")
      (node (ref "IC301") (pin "33") (pinfunction "TXDA_33") (pintype "output"))
      (node (ref "IC303") (pin "11") (pinfunction "T1IN_11") (pintype "input"))
      (node (ref "LED301") (pin "C") (pinfunction "C_C") (pintype "passive"))
    )
    (net (code "36") (name "B_RX") (class "Default")
      (node (ref "IC301") (pin "11") (pinfunction "RXDB_11") (pintype "output"))
      (node (ref "SV301") (pin "5") (pinfunction "5_5") (pintype "passive"))
    )
    (net (code "37") (name "B_TX") (class "Default")
      (node (ref "IC301") (pin "13") (pinfunction "TXDB_13") (pintype "bidirectional"))
      (node (ref "SV301") (pin "4") (pinfunction "4_4") (pintype "passive"))
    )
    (net (code "38") (name "CLK") (class "Default")
      (node (ref "IC101") (pin "15") (pinfunction "CLK_15") (pintype "input"))
      (node (ref "IC401") (pin "1") (pinfunction "IN1/CLK_1") (pintype "input"))
      (node (ref "IC402") (pin "1") (pinfunction "IN1/CLK_1") (pintype "input"))
      (node (ref "QG101") (pin "5") (pinfunction "OUT_5") (pintype "output"))
    )
    (net (code "39") (name "COM0_CTS") (class "Default")
      (node (ref "IC303") (pin "8") (pinfunction "R2IN_8") (pintype "input"))
      (node (ref "SJ301") (pin "3") (pinfunction "3_3") (pintype "passive"))
      (node (ref "SJ303") (pin "3") (pinfunction "3_3") (pintype "passive"))
    )
    (net (code "40") (name "COM0_CTS_PIN") (class "Default")
      (node (ref "SJ303") (pin "2") (pinfunction "2_2") (pintype "passive"))
      (node (ref "X301") (pin "8") (pinfunction "8_8") (pintype "passive"))
    )
    (net (code "41") (name "COM0_RTS") (class "Default")
      (node (ref "IC303") (pin "7") (pinfunction "T2OUT_7") (pintype "output"))
      (node (ref "SJ301") (pin "1") (pinfunction "1_1") (pintype "passive"))
      (node (ref "SJ303") (pin "1") (pinfunction "1_1") (pintype "passive"))
    )
    (net (code "42") (name "COM0_RTS_PIN") (class "Default")
      (node (ref "SJ301") (pin "2") (pinfunction "2_2") (pintype "passive"))
      (node (ref "X301") (pin "7") (pinfunction "7_7") (pintype "passive"))
    )
    (net (code "43") (name "COM0_RX") (class "Default")
      (node (ref "IC303") (pin "13") (pinfunction "R1IN_13") (pintype "input"))
      (node (ref "SJ302") (pin "3") (pinfunction "3_3") (pintype "passive"))
      (node (ref "SJ304") (pin "3") (pinfunction "3_3") (pintype "passive"))
    )
    (net (code "44") (name "COM0_RX_PIN") (class "Default")
      (node (ref "SJ302") (pin "2") (pinfunction "2_2") (pintype "passive"))
      (node (ref "X301") (pin "2") (pinfunction "2_2") (pintype "passive"))
    )
    (net (code "45") (name "COM0_TX") (class "Default")
      (node (ref "IC303") (pin "14") (pinfunction "T1OUT_14") (pintype "output"))
      (node (ref "SJ302") (pin "1") (pinfunction "1_1") (pintype "passive"))
      (node (ref "SJ304") (pin "1") (pinfunction "1_1") (pintype "passive"))
    )
    (net (code "46") (name "COM0_TX_PIN") (class "Default")
      (node (ref "SJ304") (pin "2") (pinfunction "2_2") (pintype "passive"))
      (node (ref "X301") (pin "3") (pinfunction "3_3") (pintype "passive"))
    )
    (net (code "47") (name "CONF0") (class "Default")
      (node (ref "IC301") (pin "40") (pinfunction "IP2_40") (pintype "input"))
      (node (ref "R311") (pin "2") (pinfunction "2_2") (pintype "passive"))
      (node (ref "S301") (pin "1") (pinfunction "1_1") (pintype "passive"))
    )
    (net (code "48") (name "CONF1") (class "Default")
      (node (ref "IC301") (pin "43") (pinfunction "IP4_43") (pintype "input"))
      (node (ref "R312") (pin "2") (pinfunction "2_2") (pintype "passive"))
      (node (ref "S301") (pin "2") (pinfunction "1_2") (pintype "passive"))
    )
    (net (code "49") (name "CONF2") (class "Default")
      (node (ref "IC301") (pin "42") (pinfunction "IP5_42") (pintype "input"))
      (node (ref "R313") (pin "2") (pinfunction "2_2") (pintype "passive"))
      (node (ref "S301") (pin "3") (pinfunction "1_3") (pintype "passive"))
    )
    (net (code "50") (name "CONF3") (class "Default")
      (node (ref "IC301") (pin "3") (pinfunction "IP3_3") (pintype "input"))
      (node (ref "R314") (pin "2") (pinfunction "2_2") (pintype "passive"))
      (node (ref "S301") (pin "4") (pinfunction "1_4") (pintype "passive"))
    )
    (net (code "51") (name "D0") (class "Default")
      (node (ref "IC101") (pin "5") (pinfunction "D0_5") (pintype "bidirectional"))
      (node (ref "IC201") (pin "13") (pinfunction "D0_13") (pintype "bidirectional"))
      (node (ref "IC203") (pin "13") (pinfunction "DQ0_13") (pintype "bidirectional"))
      (node (ref "IC301") (pin "28") (pinfunction "D0_28") (pintype "bidirectional"))
      (node (ref "IC302") (pin "11") (pinfunction "DQ0_11") (pintype "bidirectional"))
      (node (ref "R107") (pin "2") (pinfunction "2_2") (pintype "passive"))
      (node (ref "SV101") (pin "62") (pinfunction "62_62") (pintype "passive"))
    )
    (net (code "52") (name "D1") (class "Default")
      (node (ref "IC101") (pin "4") (pinfunction "D1_4") (pintype "bidirectional"))
      (node (ref "IC201") (pin "14") (pinfunction "D1_14") (pintype "bidirectional"))
      (node (ref "IC203") (pin "14") (pinfunction "DQ1_14") (pintype "bidirectional"))
      (node (ref "IC301") (pin "18") (pinfunction "D1_18") (pintype "bidirectional"))
      (node (ref "IC302") (pin "12") (pinfunction "DQ1_12") (pintype "bidirectional"))
      (node (ref "R108") (pin "2") (pinfunction "2_2") (pintype "passive"))
      (node (ref "SV101") (pin "60") (pinfunction "60_60") (pintype "passive"))
    )
    (net (code "53") (name "D2") (class "Default")
      (node (ref "IC101") (pin "3") (pinfunction "D2_3") (pintype "bidirectional"))
      (node (ref "IC201") (pin "15") (pinfunction "D2_15") (pintype "bidirectional"))
      (node (ref "IC203") (pin "15") (pinfunction "DQ2_15") (pintype "bidirectional"))
      (node (ref "IC301") (pin "27") (pinfunction "D2_27") (pintype "bidirectional"))
      (node (ref "IC302") (pin "13") (pinfunction "DQ2_13") (pintype "bidirectional"))
      (node (ref "R109") (pin "2") (pinfunction "2_2") (pintype "passive"))
      (node (ref "SV101") (pin "58") (pinfunction "58_58") (pintype "passive"))
    )
    (net (code "54") (name "D3") (class "Default")
      (node (ref "IC101") (pin "2") (pinfunction "D3_2") (pintype "bidirectional"))
      (node (ref "IC201") (pin "17") (pinfunction "D3_17") (pintype "bidirectional"))
      (node (ref "IC203") (pin "17") (pinfunction "DQ3_17") (pintype "bidirectional"))
      (node (ref "IC301") (pin "19") (pinfunction "D3_19") (pintype "bidirectional"))
      (node (ref "IC302") (pin "15") (pinfunction "DQ3_15") (pintype "bidirectional"))
      (node (ref "R110") (pin "2") (pinfunction "2_2") (pintype "passive"))
      (node (ref "SV101") (pin "56") (pinfunction "56_56") (pintype "passive"))
    )
    (net (code "55") (name "D4") (class "Default")
      (node (ref "IC101") (pin "1") (pinfunction "D4_1") (pintype "bidirectional"))
      (node (ref "IC201") (pin "18") (pinfunction "D4_18") (pintype "bidirectional"))
      (node (ref "IC203") (pin "18") (pinfunction "DQ4_18") (pintype "bidirectional"))
      (node (ref "IC301") (pin "26") (pinfunction "D4_26") (pintype "bidirectional"))
      (node (ref "IC302") (pin "16") (pinfunction "DQ4_16") (pintype "bidirectional"))
      (node (ref "R111") (pin "2") (pinfunction "2_2") (pintype "passive"))
      (node (ref "SV101") (pin "54") (pinfunction "54_54") (pintype "passive"))
    )
    (net (code "56") (name "D5") (class "Default")
      (node (ref "IC101") (pin "68") (pinfunction "D5_68") (pintype "bidirectional"))
      (node (ref "IC201") (pin "19") (pinfunction "D5_19") (pintype "bidirectional"))
      (node (ref "IC203") (pin "19") (pinfunction "DQ5_19") (pintype "bidirectional"))
      (node (ref "IC301") (pin "20") (pinfunction "D5_20") (pintype "bidirectional"))
      (node (ref "IC302") (pin "17") (pinfunction "DQ5_17") (pintype "bidirectional"))
      (node (ref "R112") (pin "2") (pinfunction "2_2") (pintype "passive"))
      (node (ref "SV101") (pin "52") (pinfunction "52_52") (pintype "passive"))
    )
    (net (code "57") (name "D6") (class "Default")
      (node (ref "IC101") (pin "67") (pinfunction "D6_67") (pintype "bidirectional"))
      (node (ref "IC201") (pin "20") (pinfunction "D6_20") (pintype "bidirectional"))
      (node (ref "IC203") (pin "20") (pinfunction "DQ6_20") (pintype "bidirectional"))
      (node (ref "IC301") (pin "25") (pinfunction "D6_25") (pintype "bidirectional"))
      (node (ref "IC302") (pin "18") (pinfunction "DQ6_18") (pintype "bidirectional"))
      (node (ref "R113") (pin "2") (pinfunction "2_2") (pintype "passive"))
      (node (ref "SV101") (pin "50") (pinfunction "50_50") (pintype "passive"))
    )
    (net (code "58") (name "D7") (class "Default")
      (node (ref "IC101") (pin "66") (pinfunction "D7_66") (pintype "bidirectional"))
      (node (ref "IC201") (pin "21") (pinfunction "D7_21") (pintype "bidirectional"))
      (node (ref "IC203") (pin "21") (pinfunction "DQ7_21") (pintype "bidirectional"))
      (node (ref "IC301") (pin "21") (pinfunction "D7_21") (pintype "bidirectional"))
      (node (ref "IC302") (pin "19") (pinfunction "DQ7_19") (pintype "bidirectional"))
      (node (ref "R114") (pin "2") (pinfunction "2_2") (pintype "passive"))
      (node (ref "SV101") (pin "48") (pinfunction "48_48") (pintype "passive"))
    )
    (net (code "59") (name "D8") (class "Default")
      (node (ref "IC101") (pin "65") (pinfunction "D8_65") (pintype "bidirectional"))
      (node (ref "IC202") (pin "13") (pinfunction "D0_13") (pintype "bidirectional"))
      (node (ref "IC204") (pin "13") (pinfunction "DQ0_13") (pintype "bidirectional"))
      (node (ref "R115") (pin "2") (pinfunction "2_2") (pintype "passive"))
      (node (ref "SV101") (pin "57") (pinfunction "57_57") (pintype "passive"))
    )
    (net (code "60") (name "D9") (class "Default")
      (node (ref "IC101") (pin "64") (pinfunction "D9_64") (pintype "bidirectional"))
      (node (ref "IC202") (pin "14") (pinfunction "D1_14") (pintype "bidirectional"))
      (node (ref "IC204") (pin "14") (pinfunction "DQ1_14") (pintype "bidirectional"))
      (node (ref "R116") (pin "2") (pinfunction "2_2") (pintype "passive"))
      (node (ref "SV101") (pin "59") (pinfunction "59_59") (pintype "passive"))
    )
    (net (code "61") (name "D10") (class "Default")
      (node (ref "IC101") (pin "63") (pinfunction "D10_63") (pintype "bidirectional"))
      (node (ref "IC202") (pin "15") (pinfunction "D2_15") (pintype "bidirectional"))
      (node (ref "IC204") (pin "15") (pinfunction "DQ2_15") (pintype "bidirectional"))
      (node (ref "R117") (pin "2") (pinfunction "2_2") (pintype "passive"))
      (node (ref "SV101") (pin "61") (pinfunction "61_61") (pintype "passive"))
    )
    (net (code "62") (name "D11") (class "Default")
      (node (ref "IC101") (pin "62") (pinfunction "D11_62") (pintype "bidirectional"))
      (node (ref "IC202") (pin "17") (pinfunction "D3_17") (pintype "bidirectional"))
      (node (ref "IC204") (pin "17") (pinfunction "DQ3_17") (pintype "bidirectional"))
      (node (ref "R118") (pin "2") (pinfunction "2_2") (pintype "passive"))
      (node (ref "SV101") (pin "55") (pinfunction "55_55") (pintype "passive"))
    )
    (net (code "63") (name "D12") (class "Default")
      (node (ref "IC101") (pin "61") (pinfunction "D12_61") (pintype "bidirectional"))
      (node (ref "IC202") (pin "18") (pinfunction "D4_18") (pintype "bidirectional"))
      (node (ref "IC204") (pin "18") (pinfunction "DQ4_18") (pintype "bidirectional"))
      (node (ref "R119") (pin "2") (pinfunction "2_2") (pintype "passive"))
      (node (ref "SV101") (pin "53") (pinfunction "53_53") (pintype "passive"))
    )
    (net (code "64") (name "D13") (class "Default")
      (node (ref "IC101") (pin "60") (pinfunction "D13_60") (pintype "bidirectional"))
      (node (ref "IC202") (pin "19") (pinfunction "D5_19") (pintype "bidirectional"))
      (node (ref "IC204") (pin "19") (pinfunction "DQ5_19") (pintype "bidirectional"))
      (node (ref "R120") (pin "2") (pinfunction "2_2") (pintype "passive"))
      (node (ref "SV101") (pin "51") (pinfunction "51_51") (pintype "passive"))
    )
    (net (code "65") (name "D14") (class "Default")
      (node (ref "IC101") (pin "59") (pinfunction "D14_59") (pintype "bidirectional"))
      (node (ref "IC202") (pin "20") (pinfunction "D6_20") (pintype "bidirectional"))
      (node (ref "IC204") (pin "20") (pinfunction "DQ6_20") (pintype "bidirectional"))
      (node (ref "R121") (pin "2") (pinfunction "2_2") (pintype "passive"))
      (node (ref "SV101") (pin "49") (pinfunction "49_49") (pintype "passive"))
    )
    (net (code "66") (name "D15") (class "Default")
      (node (ref "IC101") (pin "58") (pinfunction "D15_58") (pintype "bidirectional"))
      (node (ref "IC202") (pin "21") (pinfunction "D7_21") (pintype "bidirectional"))
      (node (ref "IC204") (pin "21") (pinfunction "DQ7_21") (pintype "bidirectional"))
      (node (ref "R122") (pin "2") (pinfunction "2_2") (pintype "passive"))
      (node (ref "SV101") (pin "47") (pinfunction "47_47") (pintype "passive"))
    )
    (net (code "67") (name "E") (class "Default")
      (node (ref "IC101") (pin "22") (pinfunction "E_22") (pintype "output"))
      (node (ref "IC405") (pin "9") (pinfunction "CLK_9") (pintype "input"))
    )
    (net (code "68") (name "FC0") (class "Default")
      (node (ref "IC101") (pin "30") (pinfunction "FC0_30") (pintype "output"))
      (node (ref "IC402") (pin "3") (pinfunction "IN3_3") (pintype "input"))
    )
    (net (code "69") (name "FC1") (class "Default")
      (node (ref "IC101") (pin "29") (pinfunction "FC1_29") (pintype "output"))
      (node (ref "IC402") (pin "4") (pinfunction "IN4_4") (pintype "input"))
    )
    (net (code "70") (name "FC2") (class "Default")
      (node (ref "IC101") (pin "28") (pinfunction "FC2_28") (pintype "output"))
      (node (ref "IC402") (pin "5") (pinfunction "IN5_5") (pintype "input"))
    )
    (net (code "71") (name "GND") (class "Default")
      (node (ref "C101") (pin "2") (pinfunction "2_2") (pintype "passive"))
      (node (ref "C102") (pin "2") (pinfunction "2_2") (pintype "passive"))
      (node (ref "C103") (pin "2") (pinfunction "2_2") (pintype "passive"))
      (node (ref "C104") (pin "2") (pinfunction "2_2") (pintype "passive"))
      (node (ref "C105") (pin "2") (pinfunction "2_2") (pintype "passive"))
      (node (ref "C106") (pin "-") (pinfunction "-_-") (pintype "passive"))
      (node (ref "C201") (pin "2") (pinfunction "2_2") (pintype "passive"))
      (node (ref "C202") (pin "2") (pinfunction "2_2") (pintype "passive"))
      (node (ref "C203") (pin "2") (pinfunction "2_2") (pintype "passive"))
      (node (ref "C204") (pin "2") (pinfunction "2_2") (pintype "passive"))
      (node (ref "C205") (pin "2") (pinfunction "2_2") (pintype "passive"))
      (node (ref "C206") (pin "2") (pinfunction "2_2") (pintype "passive"))
      (node (ref "C207") (pin "-") (pinfunction "-_-") (pintype "passive"))
      (node (ref "C208") (pin "-") (pinfunction "-_-") (pintype "passive"))
      (node (ref "C209") (pin "-") (pinfunction "-_-") (pintype "passive"))
      (node (ref "C301") (pin "1") (pinfunction "1_1") (pintype "passive"))
      (node (ref "C302") (pin "1") (pinfunction "1_1") (pintype "passive"))
      (node (ref "C305") (pin "1") (pinfunction "1_1") (pintype "passive"))
      (node (ref "C306") (pin "1") (pinfunction "1_1") (pintype "passive"))
      (node (ref "C307") (pin "2") (pinfunction "2_2") (pintype "passive"))
      (node (ref "C308") (pin "2") (pinfunction "2_2") (pintype "passive"))
      (node (ref "C309") (pin "2") (pinfunction "2_2") (pintype "passive"))
      (node (ref "C310") (pin "-") (pinfunction "-_-") (pintype "passive"))
      (node (ref "C401") (pin "2") (pinfunction "2_2") (pintype "passive"))
      (node (ref "C402") (pin "2") (pinfunction "2_2") (pintype "passive"))
      (node (ref "C403") (pin "2") (pinfunction "2_2") (pintype "passive"))
      (node (ref "C404") (pin "2") (pinfunction "2_2") (pintype "passive"))
      (node (ref "C405") (pin "2") (pinfunction "2_2") (pintype "passive"))
      (node (ref "C406") (pin "2") (pinfunction "2_2") (pintype "passive"))
      (node (ref "C407") (pin "-") (pinfunction "-_-") (pintype "passive"))
      (node (ref "IC101") (pin "16") (pinfunction "GND_16") (pintype "power_in"))
      (node (ref "IC101") (pin "17") (pinfunction "GND_17") (pintype "power_in"))
      (node (ref "IC101") (pin "56") (pinfunction "GND_56") (pintype "power_in"))
      (node (ref "IC101") (pin "57") (pinfunction "GND_57") (pintype "power_in"))
      (node (ref "IC201") (pin "16") (pinfunction "GND_16") (pintype "power_in"))
      (node (ref "IC202") (pin "16") (pinfunction "GND_16") (pintype "power_in"))
      (node (ref "IC203") (pin "16") (pinfunction "GND_16") (pintype "power_in"))
      (node (ref "IC204") (pin "16") (pinfunction "GND_16") (pintype "power_in"))
      (node (ref "IC301") (pin "22") (pinfunction "GND_22") (pintype "power_in"))
      (node (ref "IC302") (pin "14") (pinfunction "GND_14") (pintype "power_in"))
      (node (ref "IC303") (pin "15") (pinfunction "GND_15") (pintype "power_in"))
      (node (ref "IC401") (pin "12") (pinfunction "GND_12") (pintype "power_in"))
      (node (ref "IC402") (pin "12") (pinfunction "GND_12") (pintype "power_in"))
      (node (ref "IC403") (pin "1") (pinfunction "I_1") (pintype "input"))
      (node (ref "IC403") (pin "11") (pinfunction "I_11") (pintype "input"))
      (node (ref "IC403") (pin "3") (pinfunction "I_3") (pintype "input"))
      (node (ref "IC403") (pin "5") (pinfunction "I_5") (pintype "input"))
      (node (ref "IC403") (pin "7") (pinfunction "GND_7") (pintype "power_in"))
      (node (ref "IC403") (pin "9") (pinfunction "I_9") (pintype "input"))
      (node (ref "IC404") (pin "1") (pinfunction "GND_1") (pintype "power_in"))
      (node (ref "IC404") (pin "2") (pinfunction "GND_2") (pintype "power_in"))
      (node (ref "IC405") (pin "8") (pinfunction "GND_8") (pintype "power_in"))
      (node (ref "J201") (pin "GND") (pinfunction "GND_GND") (pintype "bidirectional"))
      (node (ref "J201") (pin "GNDBREAK") (pinfunction "GNDBREAK_GNDBREAK") (pintype "bidirectional"))
      (node (ref "LED201") (pin "C") (pinfunction "C_C") (pintype "passive"))
      (node (ref "LED305") (pin "C") (pinfunction "C_C") (pintype "passive"))
      (node (ref "LED306") (pin "C") (pinfunction "C_C") (pintype "passive"))
      (node (ref "LED307") (pin "C") (pinfunction "C_C") (pintype "passive"))
      (node (ref "QG101") (pin "4") (pinfunction "GND_4") (pintype "power_in"))
      (node (ref "R107") (pin "1") (pinfunction "1_1") (pintype "passive"))
      (node (ref "R108") (pin "1") (pinfunction "1_1") (pintype "passive"))
      (node (ref "R109") (pin "1") (pinfunction "1_1") (pintype "passive"))
      (node (ref "R110") (pin "1") (pinfunction "1_1") (pintype "passive"))
      (node (ref "R111") (pin "1") (pinfunction "1_1") (pintype "passive"))
      (node (ref "R112") (pin "1") (pinfunction "1_1") (pintype "passive"))
      (node (ref "R113") (pin "1") (pinfunction "1_1") (pintype "passive"))
      (node (ref "R114") (pin "1") (pinfunction "1_1") (pintype "passive"))
      (node (ref "R115") (pin "1") (pinfunction "1_1") (pintype "passive"))
      (node (ref "R116") (pin "1") (pinfunction "1_1") (pintype "passive"))
      (node (ref "R117") (pin "1") (pinfunction "1_1") (pintype "passive"))
      (node (ref "R118") (pin "1") (pinfunction "1_1") (pintype "passive"))
      (node (ref "R119") (pin "1") (pinfunction "1_1") (pintype "passive"))
      (node (ref "R120") (pin "1") (pinfunction "1_1") (pintype "passive"))
      (node (ref "R121") (pin "1") (pinfunction "1_1") (pintype "passive"))
      (node (ref "R122") (pin "1") (pinfunction "1_1") (pintype "passive"))
      (node (ref "R311") (pin "1") (pinfunction "1_1") (pintype "passive"))
      (node (ref "R312") (pin "1") (pinfunction "1_1") (pintype "passive"))
      (node (ref "R313") (pin "1") (pinfunction "1_1") (pintype "passive"))
      (node (ref "R314") (pin "1") (pinfunction "1_1") (pintype "passive"))
      (node (ref "S401") (pin "2") (pinfunction "S_2") (pintype "passive"))
      (node (ref "S402") (pin "1") (pinfunction "P_1") (pintype "passive"))
      (node (ref "SV101") (pin "17") (pinfunction "17_17") (pintype "passive"))
      (node (ref "SV101") (pin "18") (pinfunction "18_18") (pintype "passive"))
      (node (ref "SV101") (pin "3") (pinfunction "3_3") (pintype "passive"))
      (node (ref "SV101") (pin "4") (pinfunction "4_4") (pintype "passive"))
      (node (ref "SV101") (pin "43") (pinfunction "43_43") (pintype "passive"))
      (node (ref "SV101") (pin "44") (pinfunction "44_44") (pintype "passive"))
      (node (ref "SV101") (pin "45") (pinfunction "45_45") (pintype "passive"))
      (node (ref "SV101") (pin "46") (pinfunction "46_46") (pintype "passive"))
      (node (ref "SV101") (pin "63") (pinfunction "63_63") (pintype "passive"))
      (node (ref "SV101") (pin "64") (pinfunction "64_64") (pintype "passive"))
      (node (ref "SV301") (pin "1") (pinfunction "1_1") (pintype "passive"))
      (node (ref "X301") (pin "5") (pinfunction "5_5") (pintype "passive"))
      (node (ref "X301") (pin "G1") (pinfunction "G1_G1") (pintype "passive"))
      (node (ref "X301") (pin "G2") (pinfunction "G2_G2") (pintype "passive"))
    )
    (net (code "72") (name "Net-(C301-Pad2)") (class "Default")
      (node (ref "C301") (pin "2") (pinfunction "2_2") (pintype "passive"))
      (node (ref "Q301") (pin "1") (pinfunction "1_1") (pintype "passive"))
      (node (ref "R301") (pin "1") (pinfunction "1_1") (pintype "passive"))
    )
    (net (code "73") (name "Net-(C302-Pad2)") (class "Default")
      (node (ref "C302") (pin "2") (pinfunction "2_2") (pintype "passive"))
      (node (ref "Q301") (pin "2") (pinfunction "2_2") (pintype "passive"))
      (node (ref "R302") (pin "1") (pinfunction "1_1") (pintype "passive"))
    )
    (net (code "74") (name "Net-(IC303A-C1+)") (class "Default")
      (node (ref "C303") (pin "1") (pinfunction "1_1") (pintype "passive"))
      (node (ref "IC303") (pin "1") (pinfunction "C1+_1") (pintype "bidirectional"))
    )
    (net (code "75") (name "Net-(IC303A-C1-)") (class "Default")
      (node (ref "C303") (pin "2") (pinfunction "2_2") (pintype "passive"))
      (node (ref "IC303") (pin "3") (pinfunction "C1-_3") (pintype "bidirectional"))
    )
    (net (code "76") (name "Net-(IC303A-C2+)") (class "Default")
      (node (ref "C304") (pin "1") (pinfunction "1_1") (pintype "passive"))
      (node (ref "IC303") (pin "4") (pinfunction "C2+_4") (pintype "bidirectional"))
    )
    (net (code "77") (name "Net-(IC303A-C2-)") (class "Default")
      (node (ref "C304") (pin "2") (pinfunction "2_2") (pintype "passive"))
      (node (ref "IC303") (pin "5") (pinfunction "C2-_5") (pintype "bidirectional"))
    )
    (net (code "78") (name "Net-(IC303A-V+)") (class "Default")
      (node (ref "C305") (pin "2") (pinfunction "2_2") (pintype "passive"))
      (node (ref "IC303") (pin "2") (pinfunction "V+_2") (pintype "bidirectional"))
    )
    (net (code "79") (name "Net-(IC303A-V-)") (class "Default")
      (node (ref "C306") (pin "2") (pinfunction "2_2") (pintype "passive"))
      (node (ref "IC303") (pin "6") (pinfunction "V-_6") (pintype "bidirectional"))
    )
    (net (code "80") (name "Net-(IC403A-I)") (class "Default")
      (node (ref "C401") (pin "1") (pinfunction "1_1") (pintype "passive"))
      (node (ref "IC403") (pin "13") (pinfunction "I_13") (pintype "input"))
      (node (ref "R402") (pin "2") (pinfunction "2_2") (pintype "passive"))
    )
    (net (code "81") (name "Net-(IC405A-D2)") (class "Default")
      (node (ref "IC405") (pin "2") (pinfunction "Q1_2") (pintype "output"))
      (node (ref "IC405") (pin "5") (pinfunction "D2_5") (pintype "input"))
    )
    (net (code "82") (name "Net-(IC405A-D3)") (class "Default")
      (node (ref "IC405") (pin "12") (pinfunction "D3_12") (pintype "input"))
      (node (ref "IC405") (pin "7") (pinfunction "Q2_7") (pintype "output"))
    )
    (net (code "83") (name "Net-(IC405A-D4)") (class "Default")
      (node (ref "IC405") (pin "10") (pinfunction "Q3_10") (pintype "output"))
      (node (ref "IC405") (pin "13") (pinfunction "D4_13") (pintype "input"))
    )
    (net (code "84") (name "Net-(LED101-PadA)") (class "Default")
      (node (ref "LED101") (pin "A") (pinfunction "A_A") (pintype "passive"))
      (node (ref "R101") (pin "1") (pinfunction "1_1") (pintype "passive"))
    )
    (net (code "85") (name "Net-(LED102-PadA)") (class "Default")
      (node (ref "LED102") (pin "A") (pinfunction "A_A") (pintype "passive"))
      (node (ref "R102") (pin "1") (pinfunction "1_1") (pintype "passive"))
    )
    (net (code "86") (name "Net-(LED201-PadA)") (class "Default")
      (node (ref "LED201") (pin "A") (pinfunction "A_A") (pintype "passive"))
      (node (ref "R201") (pin "2") (pinfunction "2_2") (pintype "passive"))
    )
    (net (code "87") (name "Net-(LED301-PadA)") (class "Default")
      (node (ref "LED301") (pin "A") (pinfunction "A_A") (pintype "passive"))
      (node (ref "R304") (pin "1") (pinfunction "1_1") (pintype "passive"))
    )
    (net (code "88") (name "Net-(LED302-PadA)") (class "Default")
      (node (ref "LED302") (pin "A") (pinfunction "A_A") (pintype "passive"))
      (node (ref "R305") (pin "1") (pinfunction "1_1") (pintype "passive"))
    )
    (net (code "89") (name "Net-(LED303-PadA)") (class "Default")
      (node (ref "LED303") (pin "A") (pinfunction "A_A") (pintype "passive"))
      (node (ref "R306") (pin "1") (pinfunction "1_1") (pintype "passive"))
    )
    (net (code "90") (name "Net-(LED304-PadA)") (class "Default")
      (node (ref "LED304") (pin "A") (pinfunction "A_A") (pintype "passive"))
      (node (ref "R307") (pin "1") (pinfunction "1_1") (pintype "passive"))
    )
    (net (code "91") (name "Net-(LED305-PadA)") (class "Default")
      (node (ref "LED305") (pin "A") (pinfunction "A_A") (pintype "passive"))
      (node (ref "R308") (pin "2") (pinfunction "2_2") (pintype "passive"))
    )
    (net (code "92") (name "Net-(LED306-PadA)") (class "Default")
      (node (ref "LED306") (pin "A") (pinfunction "A_A") (pintype "passive"))
      (node (ref "R309") (pin "2") (pinfunction "2_2") (pintype "passive"))
    )
    (net (code "93") (name "Net-(LED307-PadA)") (class "Default")
      (node (ref "LED307") (pin "A") (pinfunction "A_A") (pintype "passive"))
      (node (ref "R310") (pin "2") (pinfunction "2_2") (pintype "passive"))
    )
    (net (code "94") (name "Net-(S401-P)") (class "Default")
      (node (ref "R401") (pin "2") (pinfunction "2_2") (pintype "passive"))
      (node (ref "R402") (pin "1") (pinfunction "1_1") (pintype "passive"))
      (node (ref "S401") (pin "1") (pinfunction "P_1") (pintype "passive"))
    )
    (net (code "95") (name "REMAP") (class "Default")
      (node (ref "IC301") (pin "31") (pinfunction "OP2_31") (pintype "output"))
      (node (ref "IC401") (pin "2") (pinfunction "IN2_2") (pintype "input"))
    )
    (net (code "96") (name "R{slash}~{W}") (class "Default")
      (node (ref "IC101") (pin "9") (pinfunction "R/W_9") (pintype "output"))
      (node (ref "IC401") (pin "3") (pinfunction "IN3_3") (pintype "input"))
      (node (ref "SV101") (pin "12") (pinfunction "12_12") (pintype "passive"))
    )
    (net (code "97") (name "STATUS0") (class "Default")
      (node (ref "IC301") (pin "16") (pinfunction "OP5_16") (pintype "output"))
      (node (ref "R310") (pin "1") (pinfunction "1_1") (pintype "passive"))
    )
    (net (code "98") (name "STATUS1") (class "Default")
      (node (ref "IC301") (pin "17") (pinfunction "OP7_17") (pintype "output"))
      (node (ref "R309") (pin "1") (pinfunction "1_1") (pintype "passive"))
    )
    (net (code "99") (name "STATUS2") (class "Default")
      (node (ref "IC301") (pin "15") (pinfunction "OP3_15") (pintype "output"))
      (node (ref "R308") (pin "1") (pinfunction "1_1") (pintype "passive"))
    )
    (net (code "100") (name "unconnected-(IC101A-VMA-Pad21)") (class "Default")
      (node (ref "IC101") (pin "21") (pinfunction "VMA_21") (pintype "output"))
    )
    (net (code "101") (name "unconnected-(IC301-OP4-Pad30)") (class "Default")
      (node (ref "IC301") (pin "30") (pinfunction "OP4_30") (pintype "output"))
    )
    (net (code "102") (name "unconnected-(IC401-IO20-Pad20)") (class "Default")
      (node (ref "IC401") (pin "20") (pinfunction "IO20_20") (pintype "bidirectional"))
    )
    (net (code "103") (name "unconnected-(IC402-IN13-Pad13)") (class "Default")
      (node (ref "IC402") (pin "13") (pinfunction "IN13_13") (pintype "input"))
    )
    (net (code "104") (name "unconnected-(IC402-IO15-Pad15)") (class "Default")
      (node (ref "IC402") (pin "15") (pinfunction "IO15_15") (pintype "bidirectional"))
    )
    (net (code "105") (name "unconnected-(IC402-IO16-Pad16)") (class "Default")
      (node (ref "IC402") (pin "16") (pinfunction "IO16_16") (pintype "bidirectional"))
    )
    (net (code "106") (name "unconnected-(IC403B-O-Pad10)") (class "Default")
      (node (ref "IC403") (pin "10") (pinfunction "O_10") (pintype "output"))
    )
    (net (code "107") (name "unconnected-(IC403C-O-Pad8)") (class "Default")
      (node (ref "IC403") (pin "8") (pinfunction "O_8") (pintype "output"))
    )
    (net (code "108") (name "unconnected-(IC403D-O-Pad2)") (class "Default")
      (node (ref "IC403") (pin "2") (pinfunction "O_2") (pintype "output"))
    )
    (net (code "109") (name "unconnected-(IC403E-O-Pad4)") (class "Default")
      (node (ref "IC403") (pin "4") (pinfunction "O_4") (pintype "output"))
    )
    (net (code "110") (name "unconnected-(IC403F-O-Pad6)") (class "Default")
      (node (ref "IC403") (pin "6") (pinfunction "O_6") (pintype "output"))
    )
    (net (code "111") (name "unconnected-(IC405A-Q4-Pad15)") (class "Default")
      (node (ref "IC405") (pin "15") (pinfunction "Q4_15") (pintype "output"))
    )
    (net (code "112") (name "unconnected-(IC405A-~{Q1}-Pad3)") (class "Default")
      (node (ref "IC405") (pin "3") (pinfunction "~{Q1}_3") (pintype "output"))
    )
    (net (code "113") (name "unconnected-(IC405A-~{Q2}-Pad6)") (class "Default")
      (node (ref "IC405") (pin "6") (pinfunction "~{Q2}_6") (pintype "output"))
    )
    (net (code "114") (name "unconnected-(IC405A-~{Q3}-Pad11)") (class "Default")
      (node (ref "IC405") (pin "11") (pinfunction "~{Q3}_11") (pintype "output"))
    )
    (net (code "115") (name "unconnected-(QG101-TS-Pad1)") (class "Default")
      (node (ref "QG101") (pin "1") (pinfunction "TS_1") (pintype "passive"))
    )
    (net (code "116") (name "unconnected-(X301-Pad1)") (class "Default")
      (node (ref "X301") (pin "1") (pinfunction "1_1") (pintype "passive"))
    )
    (net (code "117") (name "unconnected-(X301-Pad4)") (class "Default")
      (node (ref "X301") (pin "4") (pinfunction "4_4") (pintype "passive"))
    )
    (net (code "118") (name "unconnected-(X301-Pad6)") (class "Default")
      (node (ref "X301") (pin "6") (pinfunction "6_6") (pintype "passive"))
    )
    (net (code "119") (name "unconnected-(X301-Pad9)") (class "Default")
      (node (ref "X301") (pin "9") (pinfunction "9_9") (pintype "passive"))
    )
    (net (code "120") (name "~{68681_CS}") (class "Default")
      (node (ref "IC301") (pin "39") (pinfunction "~{CS}_39") (pintype "input"))
      (node (ref "IC401") (pin "22") (pinfunction "IO22_22") (pintype "bidirectional"))
    )
    (net (code "121") (name "~{68681_IRQ}") (class "Default")
      (node (ref "IC301") (pin "24") (pinfunction "~{INTR}_24") (pintype "output"))
      (node (ref "IC402") (pin "7") (pinfunction "IN7_7") (pintype "input"))
      (node (ref "R303") (pin "1") (pinfunction "1_1") (pintype "passive"))
    )
    (net (code "122") (name "~{ADDR_GOOD}") (class "Default")
      (node (ref "IC401") (pin "21") (pinfunction "IO21_21") (pintype "bidirectional"))
      (node (ref "IC402") (pin "11") (pinfunction "IN11_11") (pintype "input"))
    )
    (net (code "123") (name "~{AS}") (class "Default")
      (node (ref "IC101") (pin "6") (pinfunction "AS_6") (pintype "output"))
      (node (ref "IC401") (pin "6") (pinfunction "IN6_6") (pintype "input"))
      (node (ref "IC402") (pin "10") (pinfunction "IN10_10") (pintype "input"))
      (node (ref "SV101") (pin "13") (pinfunction "13_13") (pintype "passive"))
    )
    (net (code "124") (name "~{A_CTS}") (class "Default")
      (node (ref "IC301") (pin "8") (pinfunction "IP0_8") (pintype "input"))
      (node (ref "IC303") (pin "9") (pinfunction "R2OUT_9") (pintype "output"))
      (node (ref "LED304") (pin "C") (pinfunction "C_C") (pintype "passive"))
    )
    (net (code "125") (name "~{A_RTS}") (class "Default")
      (node (ref "IC301") (pin "32") (pinfunction "OP0_32") (pintype "output"))
      (node (ref "IC303") (pin "10") (pinfunction "T2IN_10") (pintype "input"))
      (node (ref "LED303") (pin "C") (pinfunction "C_C") (pintype "passive"))
    )
    (net (code "126") (name "~{BERR_TIMER_CLR}") (class "Default")
      (node (ref "IC402") (pin "14") (pinfunction "IO14_14") (pintype "bidirectional"))
      (node (ref "IC405") (pin "1") (pinfunction "CLR_1") (pintype "input"))
      (node (ref "IC405") (pin "4") (pinfunction "D1_4") (pintype "input"))
    )
    (net (code "127") (name "~{BERR}") (class "Default")
      (node (ref "IC101") (pin "24") (pinfunction "BERR_24") (pintype "input"))
      (node (ref "IC405") (pin "14") (pinfunction "~{Q4}_14") (pintype "output"))
    )
    (net (code "128") (name "~{BGACK}") (class "Default")
      (node (ref "IC101") (pin "12") (pinfunction "BGACK_12") (pintype "input"))
      (node (ref "SV101") (pin "8") (pinfunction "8_8") (pintype "passive"))
    )
    (net (code "129") (name "~{BG}") (class "Default")
      (node (ref "IC101") (pin "11") (pinfunction "BG_11") (pintype "output"))
      (node (ref "SV101") (pin "9") (pinfunction "9_9") (pintype "passive"))
    )
    (net (code "130") (name "~{BR}") (class "Default")
      (node (ref "IC101") (pin "13") (pinfunction "BR_13") (pintype "input"))
      (node (ref "R106") (pin "1") (pinfunction "1_1") (pintype "passive"))
      (node (ref "SV101") (pin "7") (pinfunction "7_7") (pintype "passive"))
    )
    (net (code "131") (name "~{B_CTS}") (class "Default")
      (node (ref "IC301") (pin "5") (pinfunction "IP1_5") (pintype "input"))
      (node (ref "SV301") (pin "2") (pinfunction "2_2") (pintype "passive"))
    )
    (net (code "132") (name "~{B_RTS}") (class "Default")
      (node (ref "IC301") (pin "14") (pinfunction "OP1_14") (pintype "output"))
      (node (ref "SV301") (pin "6") (pinfunction "6_6") (pintype "passive"))
    )
    (net (code "133") (name "~{DTACK}") (class "Default")
      (node (ref "IC101") (pin "10") (pinfunction "DTACK_10") (pintype "input"))
      (node (ref "IC301") (pin "10") (pinfunction "~{DTACK}_10") (pintype "output"))
      (node (ref "IC402") (pin "17") (pinfunction "IO17_17") (pintype "bidirectional"))
      (node (ref "R103") (pin "1") (pinfunction "1_1") (pintype "passive"))
      (node (ref "SV101") (pin "10") (pinfunction "10_10") (pintype "passive"))
    )
    (net (code "134") (name "~{EXTI_A}") (class "Default")
      (node (ref "IC402") (pin "8") (pinfunction "IN8_8") (pintype "input"))
      (node (ref "R403") (pin "1") (pinfunction "1_1") (pintype "passive"))
      (node (ref "SV101") (pin "16") (pinfunction "16_16") (pintype "passive"))
    )
    (net (code "135") (name "~{EXTI_B}") (class "Default")
      (node (ref "IC402") (pin "9") (pinfunction "IN9_9") (pintype "input"))
      (node (ref "R404") (pin "1") (pinfunction "1_1") (pintype "passive"))
      (node (ref "SV101") (pin "15") (pinfunction "15_15") (pintype "passive"))
    )
    (net (code "136") (name "~{EXT_ID}") (class "Default")
      (node (ref "IC301") (pin "29") (pinfunction "OP6_29") (pintype "output"))
      (node (ref "SV101") (pin "41") (pinfunction "41_41") (pintype "passive"))
    )
    (net (code "137") (name "~{HALT}") (class "Default")
      (node (ref "IC101") (pin "19") (pinfunction "HALT_19") (pintype "bidirectional"))
      (node (ref "IC402") (pin "22") (pinfunction "IO22_22") (pintype "bidirectional"))
      (node (ref "LED102") (pin "C") (pinfunction "C_C") (pintype "passive"))
      (node (ref "R105") (pin "1") (pinfunction "1_1") (pintype "passive"))
      (node (ref "SV101") (pin "5") (pinfunction "5_5") (pintype "passive"))
    )
    (net (code "138") (name "~{IPL0}") (class "Default")
      (node (ref "IC101") (pin "27") (pinfunction "IPL0_27") (pintype "input"))
      (node (ref "IC402") (pin "18") (pinfunction "IO18_18") (pintype "bidirectional"))
    )
    (net (code "139") (name "~{IPL1}") (class "Default")
      (node (ref "IC101") (pin "26") (pinfunction "IPL1_26") (pintype "input"))
      (node (ref "IC402") (pin "20") (pinfunction "IO20_20") (pintype "bidirectional"))
    )
    (net (code "140") (name "~{IPL2}") (class "Default")
      (node (ref "IC101") (pin "25") (pinfunction "IPL2_25") (pintype "input"))
      (node (ref "IC402") (pin "19") (pinfunction "IO19_19") (pintype "bidirectional"))
    )
    (net (code "141") (name "~{LDS}") (class "Default")
      (node (ref "IC101") (pin "8") (pinfunction "LDS_8") (pintype "output"))
      (node (ref "IC401") (pin "4") (pinfunction "IN4_4") (pintype "input"))
      (node (ref "SV101") (pin "11") (pinfunction "11_11") (pintype "passive"))
    )
    (net (code "142") (name "~{LOE}") (class "Default")
      (node (ref "IC201") (pin "24") (pinfunction "~{OE}_24") (pintype "input"))
      (node (ref "IC203") (pin "24") (pinfunction "~{OE}_24") (pintype "input"))
      (node (ref "IC302") (pin "22") (pinfunction "~{OE}_22") (pintype "input"))
      (node (ref "IC401") (pin "15") (pinfunction "IO15_15") (pintype "bidirectional"))
    )
    (net (code "143") (name "~{LWE}") (class "Default")
      (node (ref "IC201") (pin "29") (pinfunction "~{WE}_29") (pintype "input"))
      (node (ref "IC203") (pin "31") (pinfunction "~{WE}_31") (pintype "input"))
      (node (ref "IC301") (pin "9") (pinfunction "R/~{W}_9") (pintype "input"))
      (node (ref "IC302") (pin "27") (pinfunction "~{WE}_27") (pintype "input"))
      (node (ref "IC401") (pin "16") (pinfunction "IO16_16") (pintype "bidirectional"))
    )
    (net (code "144") (name "~{MR}") (class "Default")
      (node (ref "IC404") (pin "4") (pinfunction "~{MR}_4") (pintype "input"))
      (node (ref "S402") (pin "2") (pinfunction "S_2") (pintype "passive"))
    )
    (net (code "145") (name "~{NMI}") (class "Default")
      (node (ref "IC402") (pin "6") (pinfunction "IN6_6") (pintype "input"))
      (node (ref "IC403") (pin "12") (pinfunction "O_12") (pintype "output"))
    )
    (net (code "146") (name "~{RAM_CS}") (class "Default")
      (node (ref "IC201") (pin "22") (pinfunction "~{CE1}_22") (pintype "input"))
      (node (ref "IC202") (pin "22") (pinfunction "~{CE1}_22") (pintype "input"))
      (node (ref "IC401") (pin "14") (pinfunction "IO14_14") (pintype "bidirectional"))
    )
    (net (code "147") (name "~{RESET_IN}") (class "Default")
      (node (ref "IC402") (pin "2") (pinfunction "IN2_2") (pintype "input"))
      (node (ref "IC404") (pin "3") (pinfunction "~{RESET}_3") (pintype "output"))
    )
    (net (code "148") (name "~{RESET}") (class "Default")
      (node (ref "IC101") (pin "20") (pinfunction "RESET_20") (pintype "bidirectional"))
      (node (ref "IC301") (pin "38") (pinfunction "~{RESET}_38") (pintype "input"))
      (node (ref "IC402") (pin "23") (pinfunction "IO23_23") (pintype "bidirectional"))
      (node (ref "LED101") (pin "C") (pinfunction "C_C") (pintype "passive"))
      (node (ref "R104") (pin "1") (pinfunction "1_1") (pintype "passive"))
      (node (ref "SV101") (pin "6") (pinfunction "6_6") (pintype "passive"))
    )
    (net (code "149") (name "~{ROM_CS}") (class "Default")
      (node (ref "IC203") (pin "22") (pinfunction "~{CS}_22") (pintype "input"))
      (node (ref "IC204") (pin "22") (pinfunction "~{CS}_22") (pintype "input"))
      (node (ref "IC401") (pin "19") (pinfunction "IO19_19") (pintype "bidirectional"))
    )
    (net (code "150") (name "~{RTC_CS}") (class "Default")
      (node (ref "IC302") (pin "20") (pinfunction "~{CS}_20") (pintype "input"))
      (node (ref "IC401") (pin "23") (pinfunction "IO23_23") (pintype "bidirectional"))
    )
    (net (code "151") (name "~{UDS}") (class "Default")
      (node (ref "IC101") (pin "7") (pinfunction "UDS_7") (pintype "output"))
      (node (ref "IC401") (pin "5") (pinfunction "IN5_5") (pintype "input"))
      (node (ref "SV101") (pin "14") (pinfunction "14_14") (pintype "passive"))
    )
    (net (code "152") (name "~{UOE}") (class "Default")
      (node (ref "IC202") (pin "24") (pinfunction "~{OE}_24") (pintype "input"))
      (node (ref "IC204") (pin "24") (pinfunction "~{OE}_24") (pintype "input"))
      (node (ref "IC401") (pin "18") (pinfunction "IO18_18") (pintype "bidirectional"))
    )
    (net (code "153") (name "~{UWE}") (class "Default")
      (node (ref "IC202") (pin "29") (pinfunction "~{WE}_29") (pintype "input"))
      (node (ref "IC204") (pin "31") (pinfunction "~{WE}_31") (pintype "input"))
      (node (ref "IC401") (pin "17") (pinfunction "IO17_17") (pintype "bidirectional"))
    )
    (net (code "154") (name "~{VPA}") (class "Default")
      (node (ref "IC101") (pin "23") (pinfunction "VPA_23") (pintype "input"))
      (node (ref "IC402") (pin "21") (pinfunction "IO21_21") (pintype "bidirectional"))
    )
  )
)
